# VerdiRT7_MainPCB.net
KiCad netlist of a schematic drawn in EAGLE
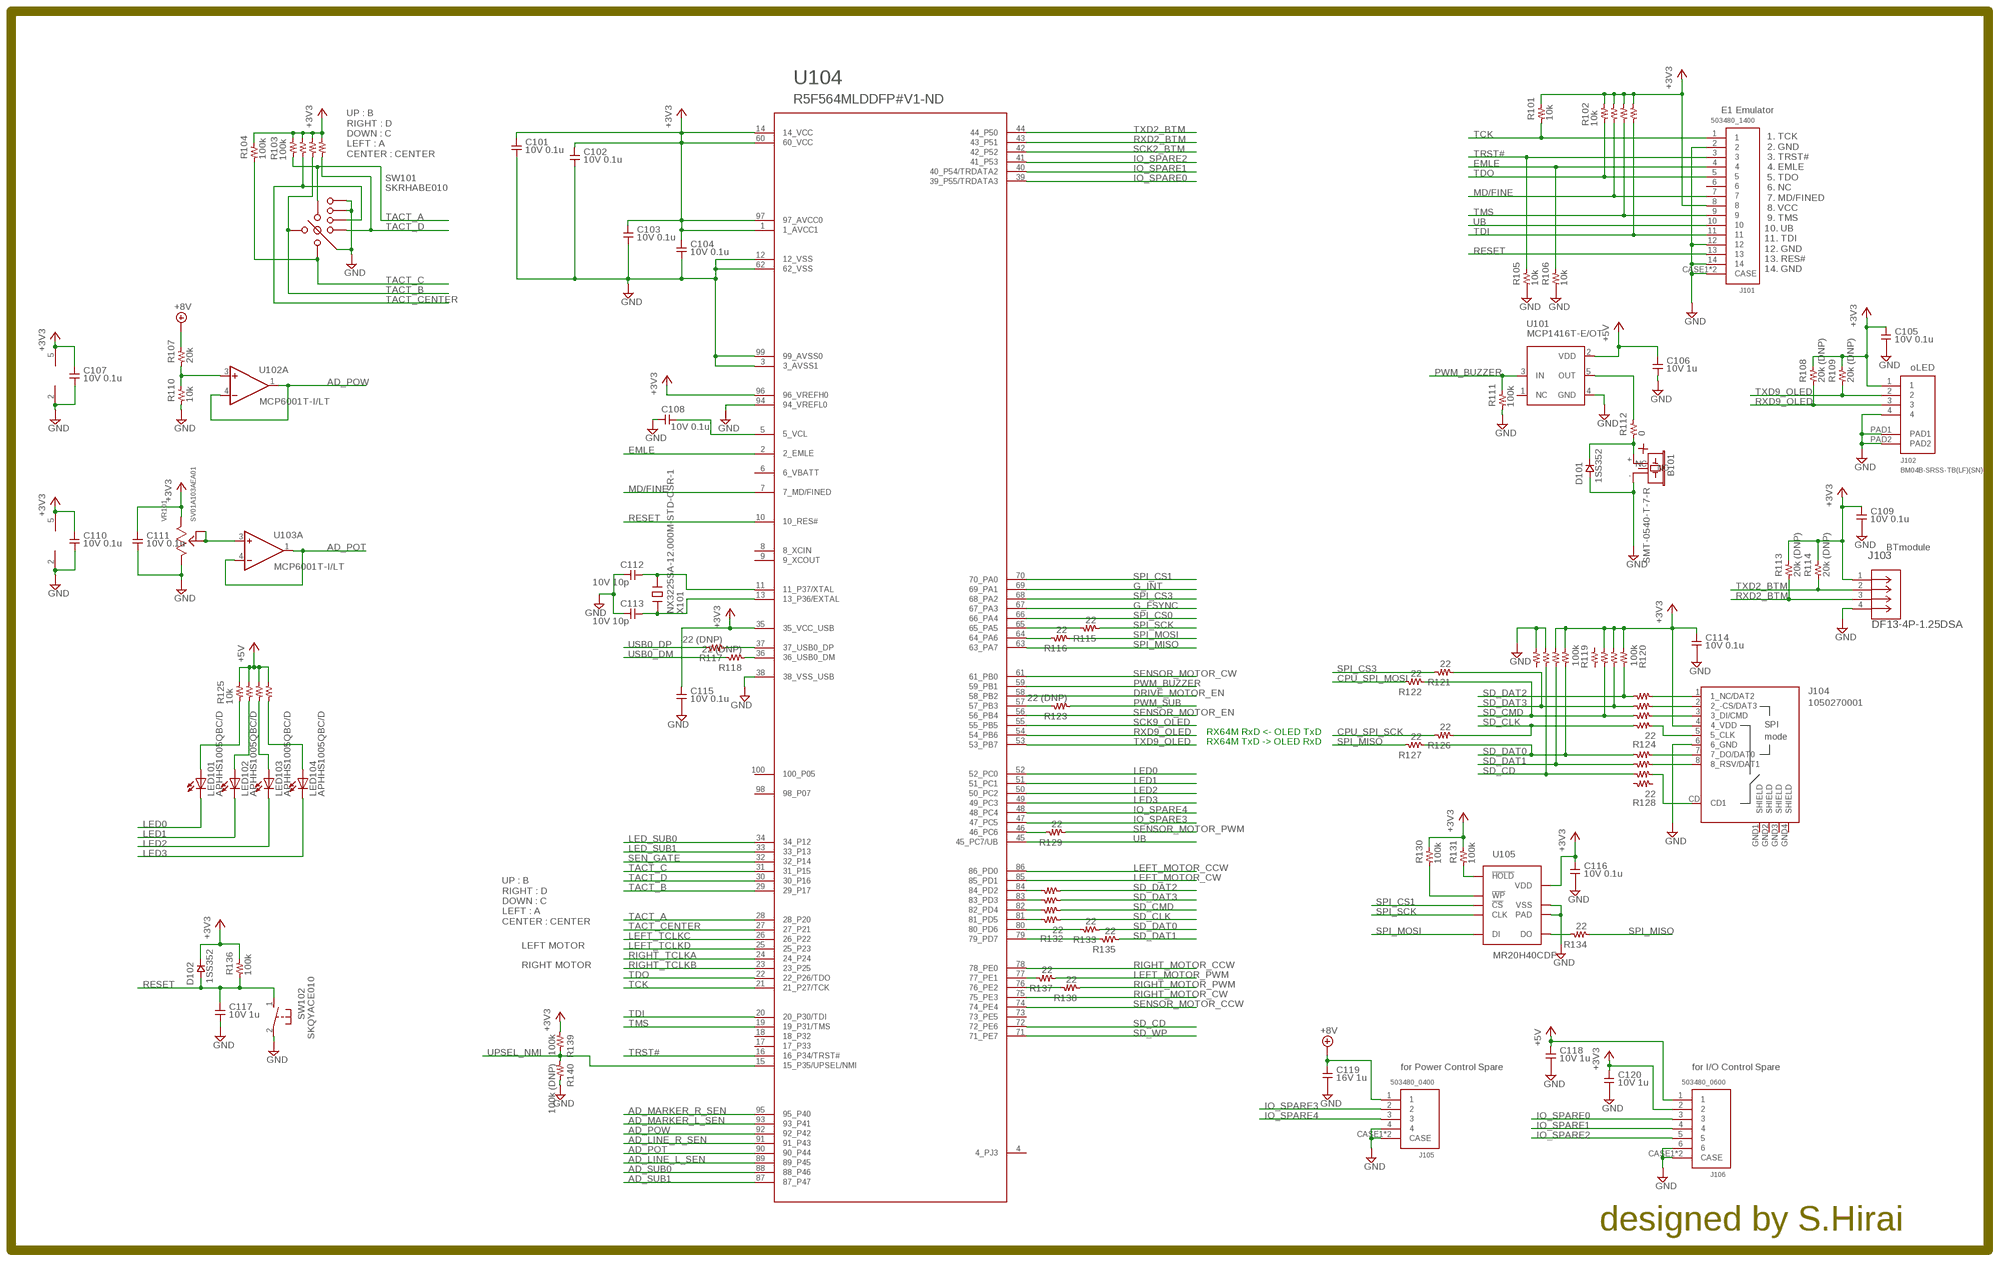
[diagram p0: schematic, sheet 1]
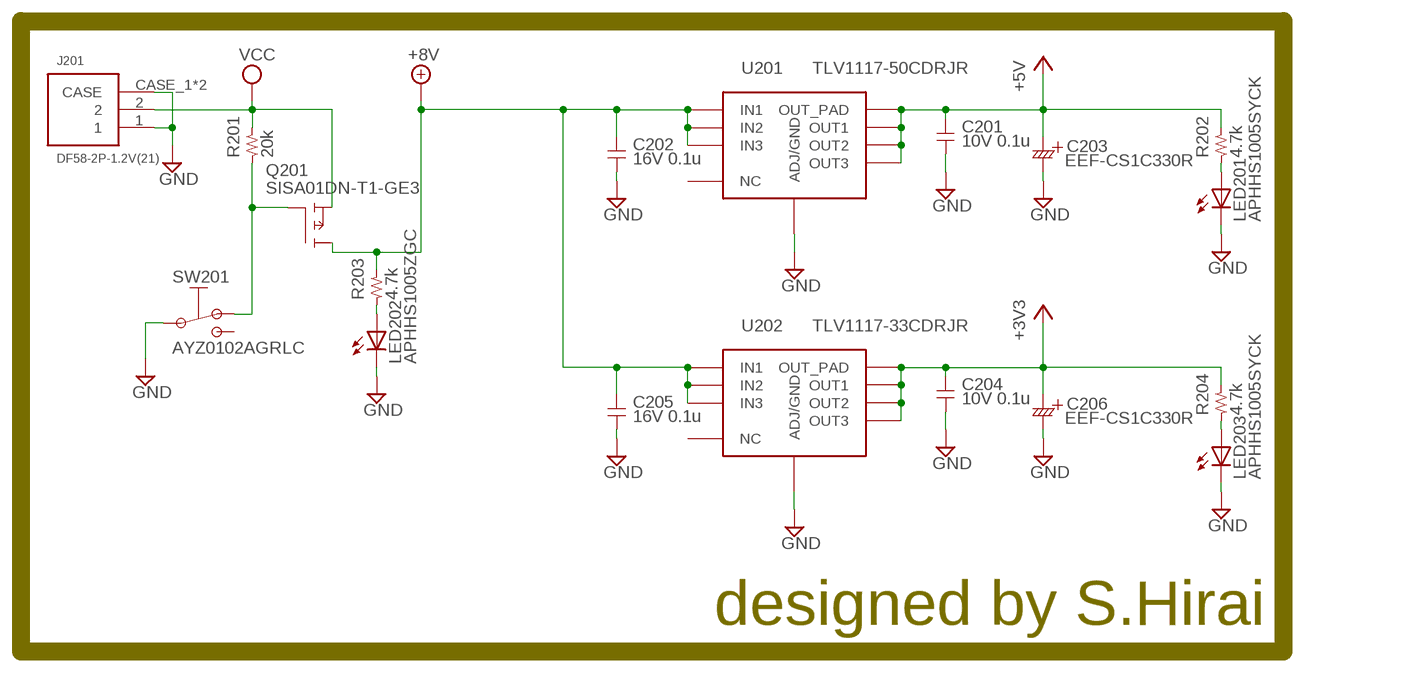
[diagram p1: schematic, sheet 2]
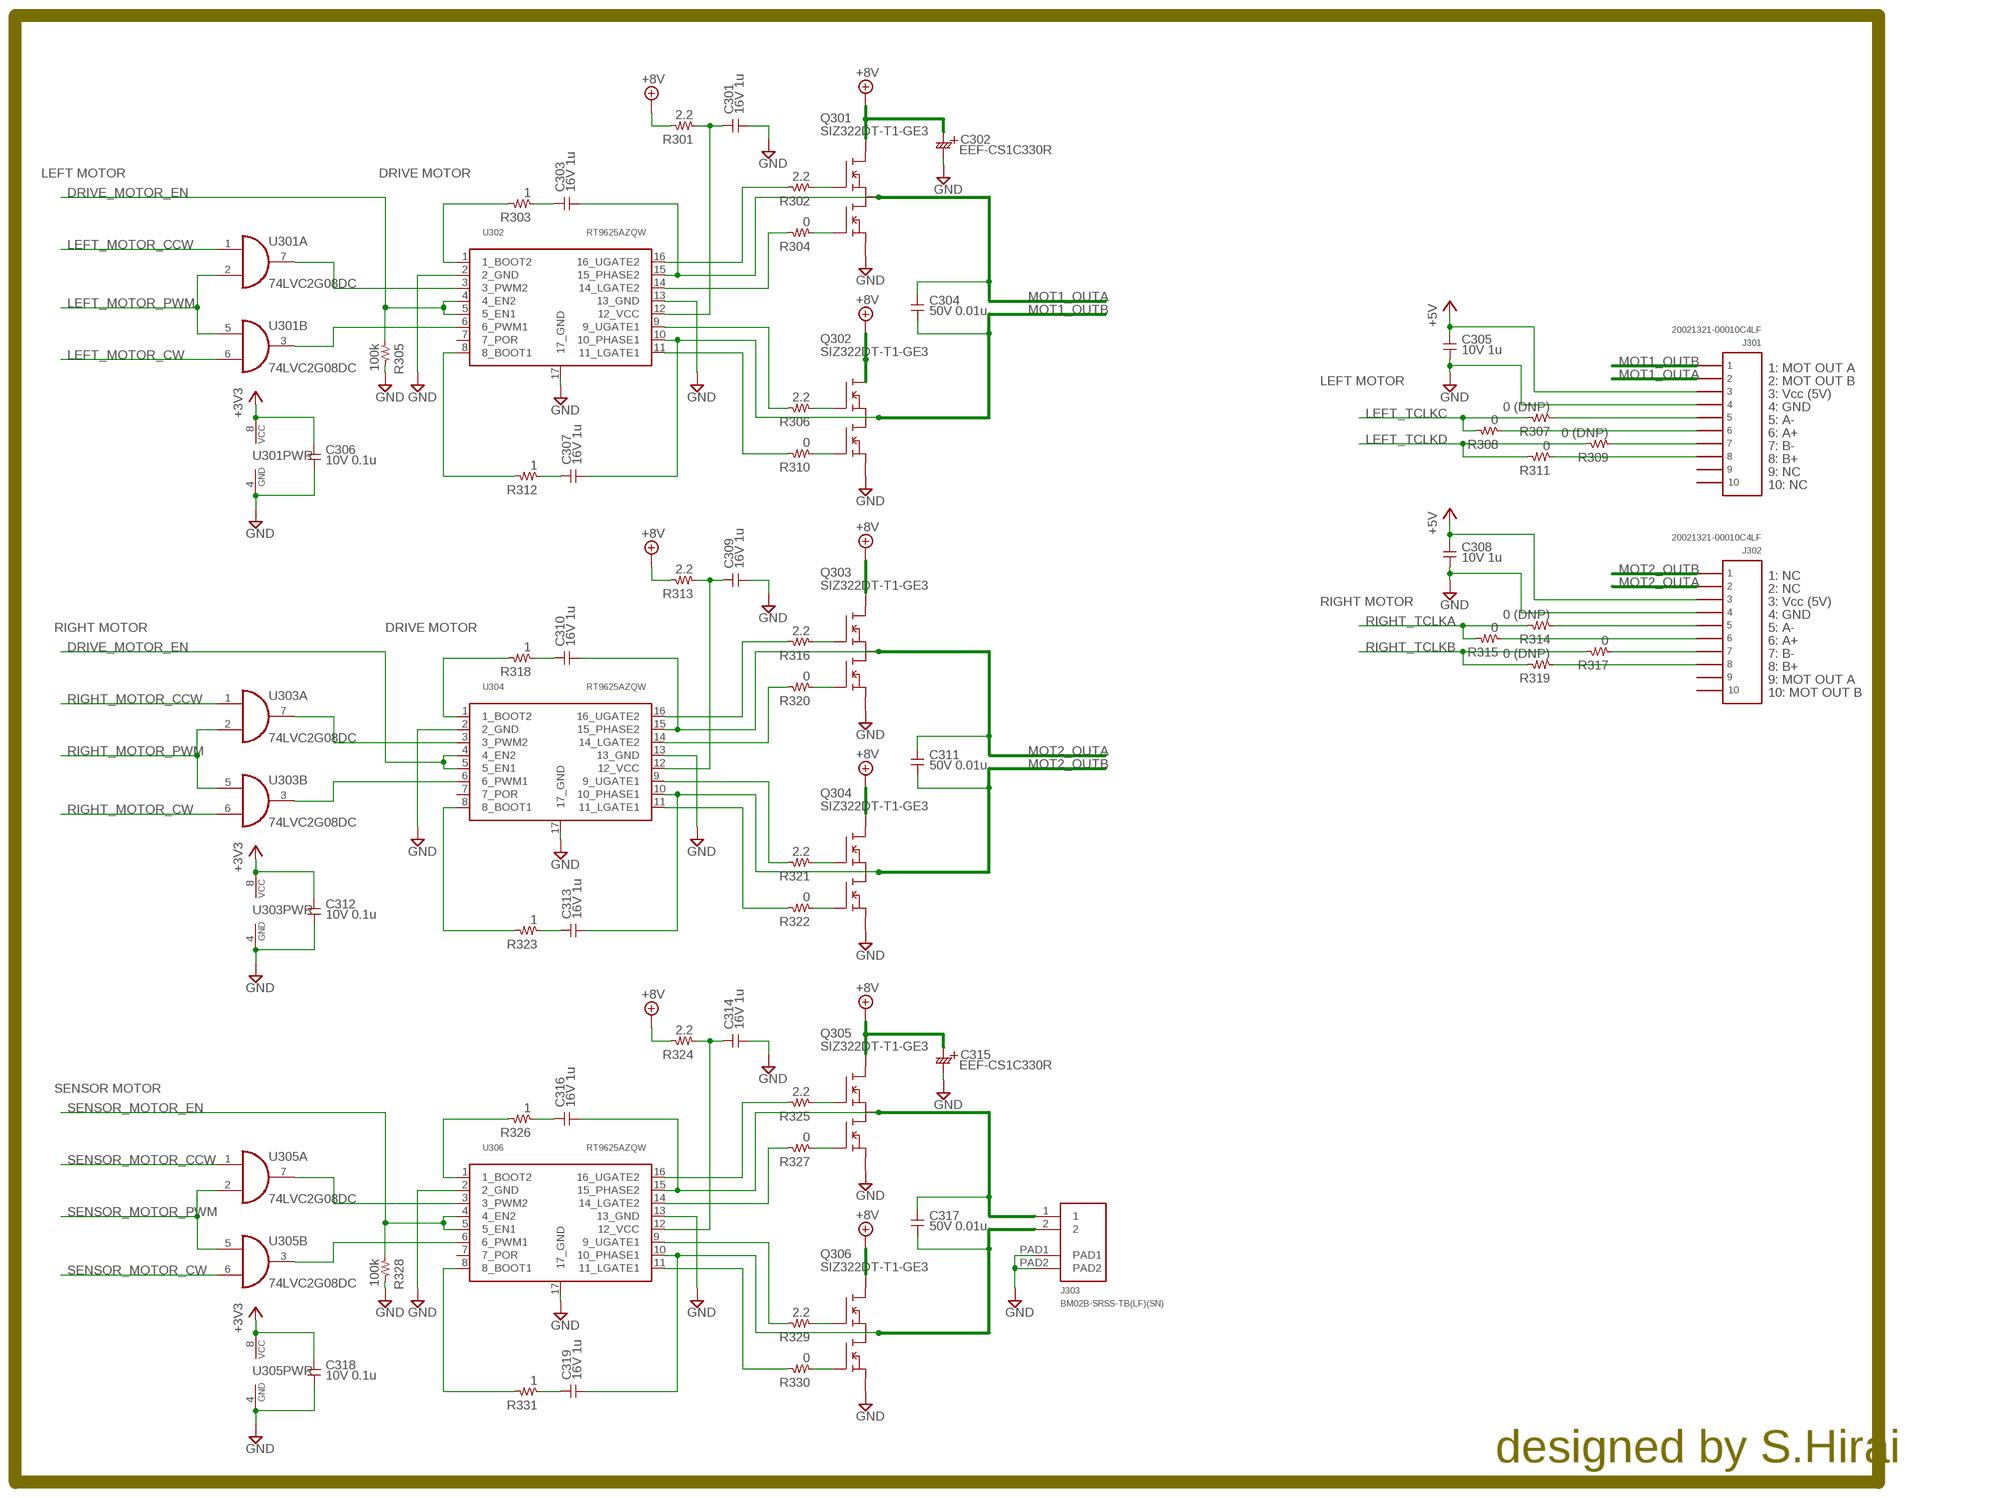
[diagram p2: schematic, sheet 3]
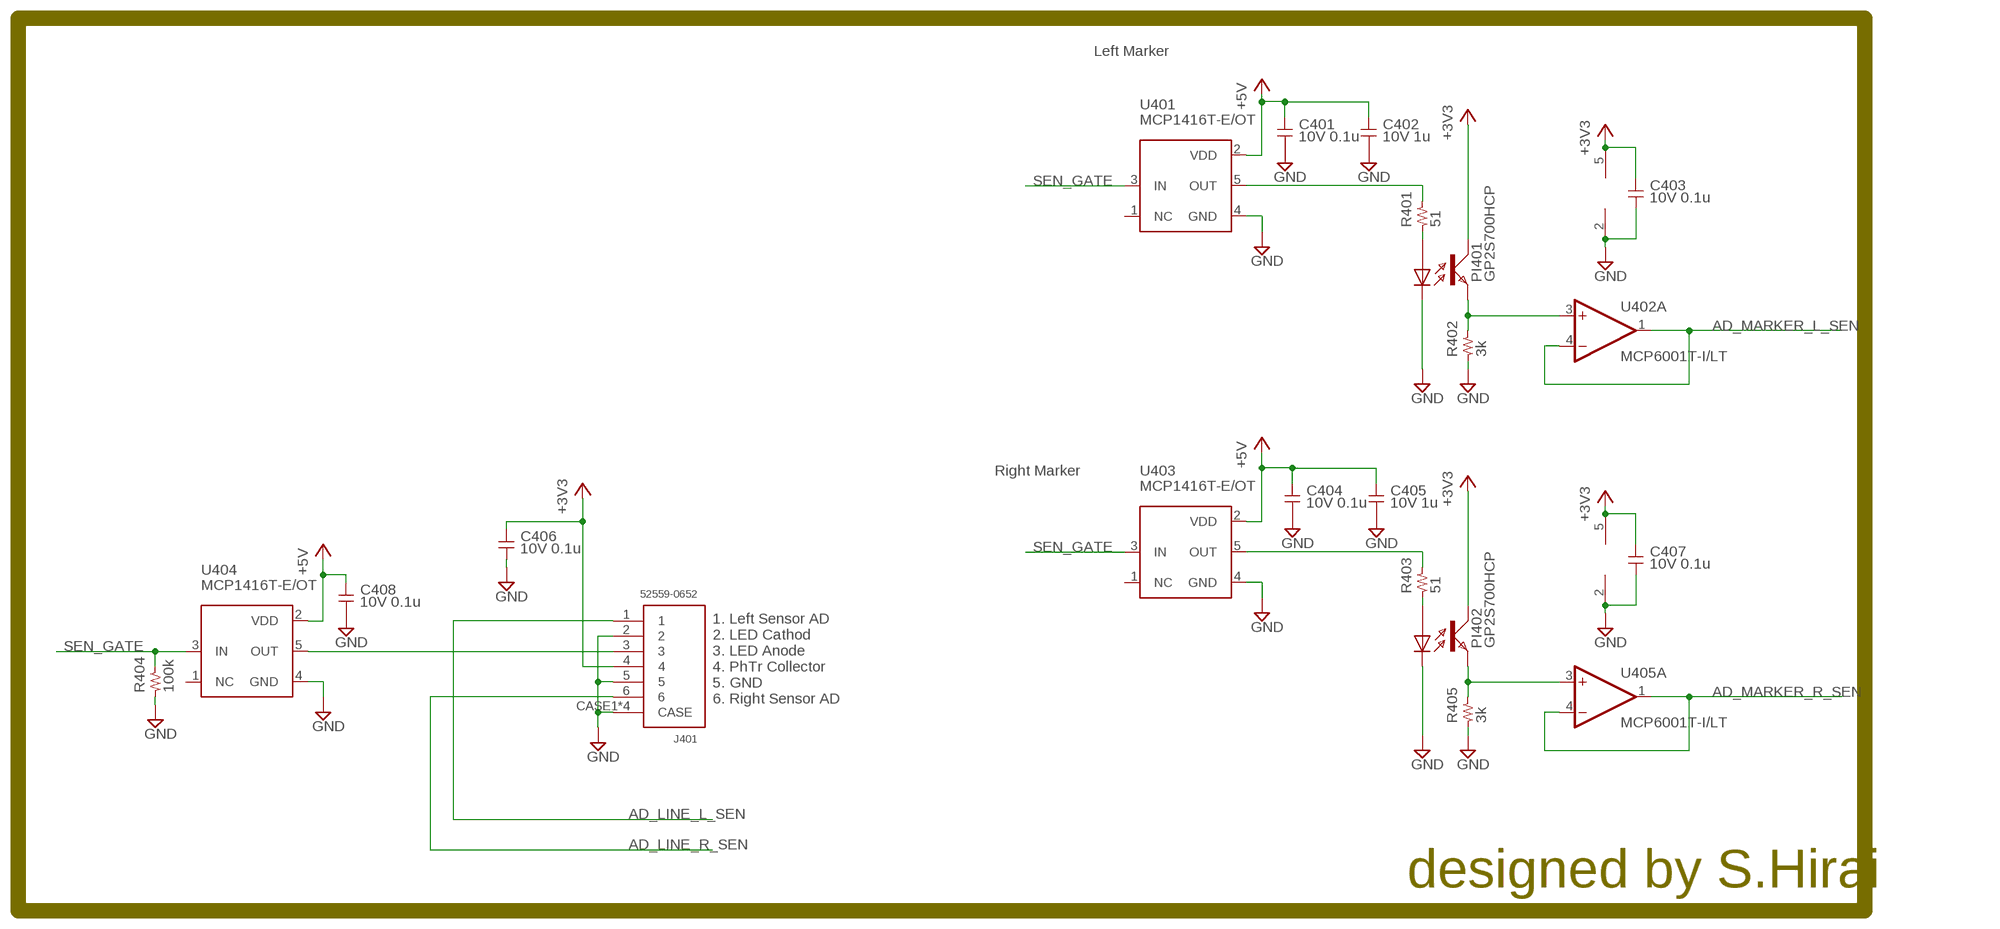
[diagram p3: schematic, sheet 4]
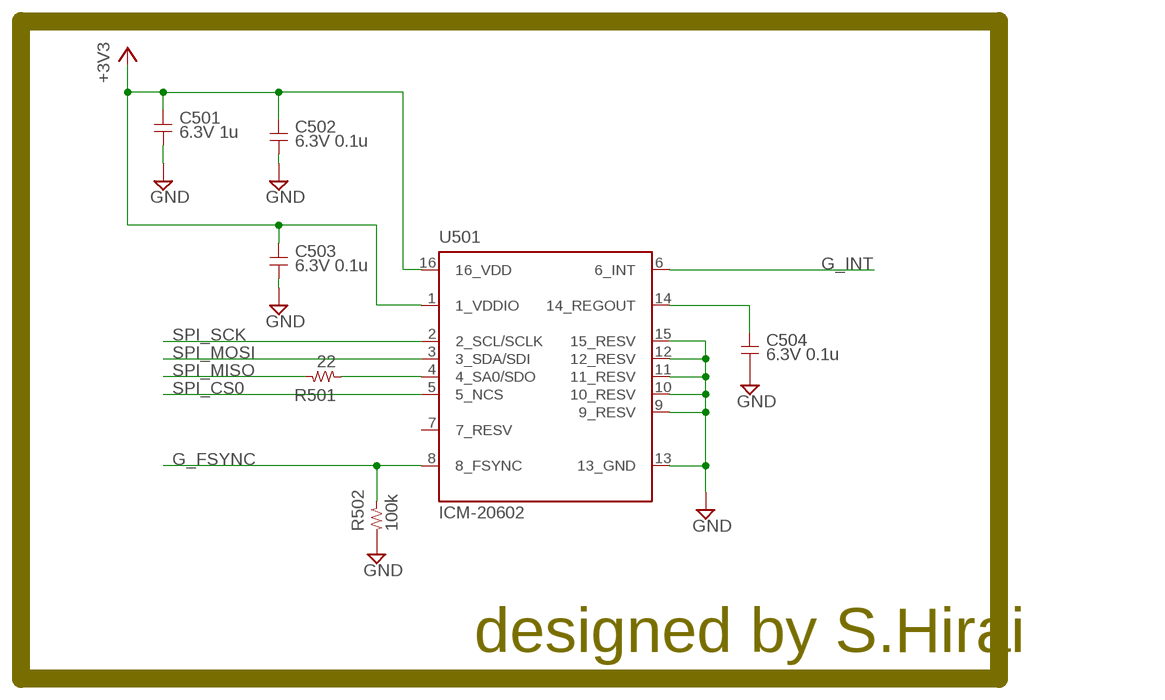
[diagram p4: schematic, sheet 5]
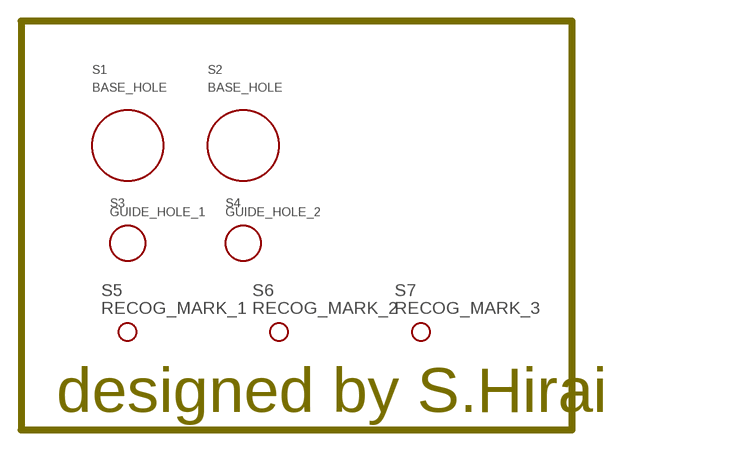
[diagram p5: schematic, sheet 6]

(export (version "E")
  (design (tool "Eeschema 10.0.6"))
  (components
    (comp (ref "C301")
      (value "16V 1u")
      (footprint "eagle-import:1005")
      (libsource (lib "eagle-import") (part "1005"))
    )
    (comp (ref "C302")
      (value "EEF-CS1C330R")
      (footprint "eagle-import:EEFC_7343")
      (fields (field (name "VOLTAGE") "16V"))
      (libsource (lib "eagle-import") (part "EEF-C?RS1C330"))
    )
    (comp (ref "C303")
      (value "16V 1u")
      (footprint "eagle-import:1005")
      (libsource (lib "eagle-import") (part "1005"))
    )
    (comp (ref "C304")
      (value "50V 0.01u")
      (footprint "eagle-import:1005")
      (libsource (lib "eagle-import") (part "1005"))
    )
    (comp (ref "C305")
      (value "10V 1u")
      (footprint "eagle-import:1005")
      (libsource (lib "eagle-import") (part "1005"))
    )
    (comp (ref "C306")
      (value "10V 0.1u")
      (footprint "eagle-import:1005")
      (libsource (lib "eagle-import") (part "1005"))
    )
    (comp (ref "C307")
      (value "16V 1u")
      (footprint "eagle-import:1005")
      (libsource (lib "eagle-import") (part "1005"))
    )
    (comp (ref "C308")
      (value "10V 1u")
      (footprint "eagle-import:1005")
      (libsource (lib "eagle-import") (part "1005"))
    )
    (comp (ref "C309")
      (value "16V 1u")
      (footprint "eagle-import:1005")
      (libsource (lib "eagle-import") (part "1005"))
    )
    (comp (ref "C310")
      (value "16V 1u")
      (footprint "eagle-import:1005")
      (libsource (lib "eagle-import") (part "1005"))
    )
    (comp (ref "C311")
      (value "50V 0.01u")
      (footprint "eagle-import:1005")
      (libsource (lib "eagle-import") (part "1005"))
    )
    (comp (ref "C312")
      (value "10V 0.1u")
      (footprint "eagle-import:1005")
      (libsource (lib "eagle-import") (part "1005"))
    )
    (comp (ref "C313")
      (value "16V 1u")
      (footprint "eagle-import:1005")
      (libsource (lib "eagle-import") (part "1005"))
    )
    (comp (ref "C314")
      (value "16V 1u")
      (footprint "eagle-import:1005")
      (libsource (lib "eagle-import") (part "1005"))
    )
    (comp (ref "C315")
      (value "EEF-CS1C330R")
      (footprint "eagle-import:EEFC_7343")
      (fields (field (name "VOLTAGE") "16V"))
      (libsource (lib "eagle-import") (part "EEF-C?RS1C330"))
    )
    (comp (ref "C316")
      (value "16V 1u")
      (footprint "eagle-import:1005")
      (libsource (lib "eagle-import") (part "1005"))
    )
    (comp (ref "C317")
      (value "50V 0.01u")
      (footprint "eagle-import:1005")
      (libsource (lib "eagle-import") (part "1005"))
    )
    (comp (ref "C318")
      (value "10V 0.1u")
      (footprint "eagle-import:1005")
      (libsource (lib "eagle-import") (part "1005"))
    )
    (comp (ref "C319")
      (value "16V 1u")
      (footprint "eagle-import:1005")
      (libsource (lib "eagle-import") (part "1005"))
    )
    (comp (ref "J301")
      (value "20021321-00010C4LF")
      (footprint "eagle-import:MA5-2_SMD_1.27MM_MIN")
      (libsource (lib "eagle-import") (part "20021321-00010C4LF"))
    )
    (comp (ref "J302")
      (value "20021321-00010C4LF")
      (footprint "eagle-import:MA5-2_SMD_1.27MM_MIN")
      (libsource (lib "eagle-import") (part "20021321-00010C4LF"))
    )
    (comp (ref "J303")
      (value "BM02B-SRSS-TB(LF)(SN)")
      (footprint "eagle-import:BM02B-SRSS-TB")
      (libsource (lib "eagle-import") (part "?M02B-SRSS-TB(LF)(SN)B"))
    )
    (comp (ref "Q301")
      (value "SIZ322DT-T1-GE3")
      (footprint "eagle-import:DFN3X3A")
      (libsource (lib "eagle-import") (part "SIZ322DT-T1-GE3"))
    )
    (comp (ref "Q302")
      (value "SIZ322DT-T1-GE3")
      (footprint "eagle-import:DFN3X3A")
      (libsource (lib "eagle-import") (part "SIZ322DT-T1-GE3"))
    )
    (comp (ref "Q303")
      (value "SIZ322DT-T1-GE3")
      (footprint "eagle-import:DFN3X3A")
      (libsource (lib "eagle-import") (part "SIZ322DT-T1-GE3"))
    )
    (comp (ref "Q304")
      (value "SIZ322DT-T1-GE3")
      (footprint "eagle-import:DFN3X3A")
      (libsource (lib "eagle-import") (part "SIZ322DT-T1-GE3"))
    )
    (comp (ref "Q305")
      (value "SIZ322DT-T1-GE3")
      (footprint "eagle-import:DFN3X3A")
      (libsource (lib "eagle-import") (part "SIZ322DT-T1-GE3"))
    )
    (comp (ref "Q306")
      (value "SIZ322DT-T1-GE3")
      (footprint "eagle-import:DFN3X3A")
      (libsource (lib "eagle-import") (part "SIZ322DT-T1-GE3"))
    )
    (comp (ref "R301")
      (value "2.2")
      (footprint "eagle-import:1005")
      (libsource (lib "eagle-import") (part "R1005"))
    )
    (comp (ref "R302")
      (value "2.2")
      (footprint "eagle-import:1005")
      (libsource (lib "eagle-import") (part "R1005"))
    )
    (comp (ref "R303")
      (value "1")
      (footprint "eagle-import:1005")
      (libsource (lib "eagle-import") (part "R1005"))
    )
    (comp (ref "R304")
      (value "0")
      (footprint "eagle-import:1005")
      (libsource (lib "eagle-import") (part "R1005"))
    )
    (comp (ref "R305")
      (value "100k")
      (footprint "eagle-import:1005")
      (libsource (lib "eagle-import") (part "R1005"))
    )
    (comp (ref "R306")
      (value "2.2")
      (footprint "eagle-import:1005")
      (libsource (lib "eagle-import") (part "R1005"))
    )
    (comp (ref "R307")
      (value "0 (DNP)")
      (footprint "eagle-import:1005")
      (libsource (lib "eagle-import") (part "R1005"))
    )
    (comp (ref "R308")
      (value "0")
      (footprint "eagle-import:1005")
      (libsource (lib "eagle-import") (part "R1005"))
    )
    (comp (ref "R309")
      (value "0 (DNP)")
      (footprint "eagle-import:1005")
      (libsource (lib "eagle-import") (part "R1005"))
    )
    (comp (ref "R310")
      (value "0")
      (footprint "eagle-import:1005")
      (libsource (lib "eagle-import") (part "R1005"))
    )
    (comp (ref "R311")
      (value "0")
      (footprint "eagle-import:1005")
      (libsource (lib "eagle-import") (part "R1005"))
    )
    (comp (ref "R312")
      (value "1")
      (footprint "eagle-import:1005")
      (libsource (lib "eagle-import") (part "R1005"))
    )
    (comp (ref "R313")
      (value "2.2")
      (footprint "eagle-import:1005")
      (libsource (lib "eagle-import") (part "R1005"))
    )
    (comp (ref "R314")
      (value "0 (DNP)")
      (footprint "eagle-import:1005")
      (libsource (lib "eagle-import") (part "R1005"))
    )
    (comp (ref "R315")
      (value "0")
      (footprint "eagle-import:1005")
      (libsource (lib "eagle-import") (part "R1005"))
    )
    (comp (ref "R316")
      (value "2.2")
      (footprint "eagle-import:1005")
      (libsource (lib "eagle-import") (part "R1005"))
    )
    (comp (ref "R317")
      (value "0")
      (footprint "eagle-import:1005")
      (libsource (lib "eagle-import") (part "R1005"))
    )
    (comp (ref "R318")
      (value "1")
      (footprint "eagle-import:1005")
      (libsource (lib "eagle-import") (part "R1005"))
    )
    (comp (ref "R319")
      (value "0 (DNP)")
      (footprint "eagle-import:1005")
      (libsource (lib "eagle-import") (part "R1005"))
    )
    (comp (ref "R320")
      (value "0")
      (footprint "eagle-import:1005")
      (libsource (lib "eagle-import") (part "R1005"))
    )
    (comp (ref "R321")
      (value "2.2")
      (footprint "eagle-import:1005")
      (libsource (lib "eagle-import") (part "R1005"))
    )
    (comp (ref "R322")
      (value "0")
      (footprint "eagle-import:1005")
      (libsource (lib "eagle-import") (part "R1005"))
    )
    (comp (ref "R323")
      (value "1")
      (footprint "eagle-import:1005")
      (libsource (lib "eagle-import") (part "R1005"))
    )
    (comp (ref "R324")
      (value "2.2")
      (footprint "eagle-import:1005")
      (libsource (lib "eagle-import") (part "R1005"))
    )
    (comp (ref "R325")
      (value "2.2")
      (footprint "eagle-import:1005")
      (libsource (lib "eagle-import") (part "R1005"))
    )
    (comp (ref "R326")
      (value "1")
      (footprint "eagle-import:1005")
      (libsource (lib "eagle-import") (part "R1005"))
    )
    (comp (ref "R327")
      (value "0")
      (footprint "eagle-import:1005")
      (libsource (lib "eagle-import") (part "R1005"))
    )
    (comp (ref "R328")
      (value "100k")
      (footprint "eagle-import:1005")
      (libsource (lib "eagle-import") (part "R1005"))
    )
    (comp (ref "R329")
      (value "2.2")
      (footprint "eagle-import:1005")
      (libsource (lib "eagle-import") (part "R1005"))
    )
    (comp (ref "R330")
      (value "0")
      (footprint "eagle-import:1005")
      (libsource (lib "eagle-import") (part "R1005"))
    )
    (comp (ref "R331")
      (value "1")
      (footprint "eagle-import:1005")
      (libsource (lib "eagle-import") (part "R1005"))
    )
    (comp (ref "U301")
      (value "74LVC2G08DC")
      (footprint "eagle-import:VSSOP8")
      (libsource (lib "eagle-import") (part "74LVC2G08DC"))
    )
    (comp (ref "U302")
      (value "RT9625AZQW")
      (footprint "eagle-import:WQFN16")
      (libsource (lib "eagle-import") (part "RT9625AZQW"))
    )
    (comp (ref "U303")
      (value "74LVC2G08DC")
      (footprint "eagle-import:VSSOP8")
      (libsource (lib "eagle-import") (part "74LVC2G08DC"))
    )
    (comp (ref "U304")
      (value "RT9625AZQW")
      (footprint "eagle-import:WQFN16")
      (libsource (lib "eagle-import") (part "RT9625AZQW"))
    )
    (comp (ref "U305")
      (value "74LVC2G08DC")
      (footprint "eagle-import:VSSOP8")
      (libsource (lib "eagle-import") (part "74LVC2G08DC"))
    )
    (comp (ref "U306")
      (value "RT9625AZQW")
      (footprint "eagle-import:WQFN16")
      (libsource (lib "eagle-import") (part "RT9625AZQW"))
    )
    (comp (ref "C501")
      (value "6.3V 1u")
      (footprint "eagle-import:1005")
      (libsource (lib "eagle-import") (part "1005"))
    )
    (comp (ref "C502")
      (value "6.3V 0.1u")
      (footprint "eagle-import:1005")
      (libsource (lib "eagle-import") (part "1005"))
    )
    (comp (ref "C503")
      (value "6.3V 0.1u")
      (footprint "eagle-import:1005")
      (libsource (lib "eagle-import") (part "1005"))
    )
    (comp (ref "C504")
      (value "6.3V 0.1u")
      (footprint "eagle-import:1005")
      (libsource (lib "eagle-import") (part "1005"))
    )
    (comp (ref "R501")
      (value "22")
      (footprint "eagle-import:1005")
      (libsource (lib "eagle-import") (part "R1005"))
    )
    (comp (ref "R502")
      (value "100k")
      (footprint "eagle-import:1005")
      (libsource (lib "eagle-import") (part "R1005"))
    )
    (comp (ref "U501")
      (value "ICM-20602")
      (footprint "eagle-import:LGA16_3X3MM")
      (libsource (lib "eagle-import") (part "ICM-20602"))
    )
    (comp (ref "C401")
      (value "10V 0.1u")
      (footprint "eagle-import:1005")
      (libsource (lib "eagle-import") (part "1005"))
    )
    (comp (ref "C402")
      (value "10V 1u")
      (footprint "eagle-import:1005")
      (libsource (lib "eagle-import") (part "1005"))
    )
    (comp (ref "C403")
      (value "10V 0.1u")
      (footprint "eagle-import:1005")
      (libsource (lib "eagle-import") (part "1005"))
    )
    (comp (ref "C404")
      (value "10V 0.1u")
      (footprint "eagle-import:1005")
      (libsource (lib "eagle-import") (part "1005"))
    )
    (comp (ref "C405")
      (value "10V 1u")
      (footprint "eagle-import:1005")
      (libsource (lib "eagle-import") (part "1005"))
    )
    (comp (ref "C406")
      (value "10V 0.1u")
      (footprint "eagle-import:1005")
      (libsource (lib "eagle-import") (part "1005"))
    )
    (comp (ref "C407")
      (value "10V 0.1u")
      (footprint "eagle-import:1005")
      (libsource (lib "eagle-import") (part "1005"))
    )
    (comp (ref "C408")
      (value "10V 0.1u")
      (footprint "eagle-import:1005")
      (libsource (lib "eagle-import") (part "1005"))
    )
    (comp (ref "J401")
      (value "52559-0652")
      (footprint "eagle-import:0652")
      (libsource (lib "eagle-import") (part "52559-0652"))
    )
    (comp (ref "PI401")
      (value "GP2S700HCP")
      (footprint "eagle-import:GP2S700")
      (libsource (lib "eagle-import") (part "GP2S700HCP"))
    )
    (comp (ref "PI402")
      (value "GP2S700HCP")
      (footprint "eagle-import:GP2S700")
      (libsource (lib "eagle-import") (part "GP2S700HCP"))
    )
    (comp (ref "R401")
      (value "51")
      (footprint "eagle-import:1608")
      (libsource (lib "eagle-import") (part "R1608"))
    )
    (comp (ref "R402")
      (value "3k")
      (footprint "eagle-import:1005")
      (libsource (lib "eagle-import") (part "R1005"))
    )
    (comp (ref "R403")
      (value "51")
      (footprint "eagle-import:1608")
      (libsource (lib "eagle-import") (part "R1608"))
    )
    (comp (ref "R404")
      (value "100k")
      (footprint "eagle-import:1005")
      (libsource (lib "eagle-import") (part "R1005"))
    )
    (comp (ref "R405")
      (value "3k")
      (footprint "eagle-import:1005")
      (libsource (lib "eagle-import") (part "R1005"))
    )
    (comp (ref "U401")
      (value "MCP1416T-E/OT")
      (footprint "eagle-import:SOT23-5")
      (libsource (lib "eagle-import") (part "MCP1416?T-E/OT"))
    )
    (comp (ref "U402")
      (value "MCP6001T-I/LT")
      (footprint "eagle-import:SOT-70-5")
      (libsource (lib "eagle-import") (part "MCP6001?-TI/LT"))
    )
    (comp (ref "U403")
      (value "MCP1416T-E/OT")
      (footprint "eagle-import:SOT23-5")
      (libsource (lib "eagle-import") (part "MCP1416?T-E/OT"))
    )
    (comp (ref "U404")
      (value "MCP1416T-E/OT")
      (footprint "eagle-import:SOT23-5")
      (libsource (lib "eagle-import") (part "MCP1416?T-E/OT"))
    )
    (comp (ref "U405")
      (value "MCP6001T-I/LT")
      (footprint "eagle-import:SOT-70-5")
      (libsource (lib "eagle-import") (part "MCP6001?-TI/LT"))
    )
    (comp (ref "C201")
      (value "10V 0.1u")
      (footprint "eagle-import:1005")
      (libsource (lib "eagle-import") (part "1005"))
    )
    (comp (ref "C202")
      (value "16V 0.1u")
      (footprint "eagle-import:1005")
      (libsource (lib "eagle-import") (part "1005"))
    )
    (comp (ref "C203")
      (value "EEF-CS1C330R")
      (footprint "eagle-import:EEFC_7343")
      (fields (field (name "VOLTAGE") "16V"))
      (libsource (lib "eagle-import") (part "EEF-C?RS1C330"))
    )
    (comp (ref "C204")
      (value "10V 0.1u")
      (footprint "eagle-import:1005")
      (libsource (lib "eagle-import") (part "1005"))
    )
    (comp (ref "C205")
      (value "16V 0.1u")
      (footprint "eagle-import:1005")
      (libsource (lib "eagle-import") (part "1005"))
    )
    (comp (ref "C206")
      (value "EEF-CS1C330R")
      (footprint "eagle-import:EEFC_7343")
      (fields (field (name "VOLTAGE") "16V"))
      (libsource (lib "eagle-import") (part "EEF-C?RS1C330"))
    )
    (comp (ref "J201")
      (value "DF58-2P-1.2V(21)")
      (footprint "eagle-import:DF58_2P")
      (libsource (lib "eagle-import") (part "DF58-2P-1.2V(21)"))
    )
    (comp (ref "LED201")
      (value "APHHS1005SYCK")
      (footprint "eagle-import:1005")
      (libsource (lib "eagle-import") (part "LED1005"))
    )
    (comp (ref "LED202")
      (value "APHHS1005ZGC")
      (footprint "eagle-import:1005")
      (libsource (lib "eagle-import") (part "LED1005"))
    )
    (comp (ref "LED203")
      (value "APHHS1005SYCK")
      (footprint "eagle-import:1005")
      (libsource (lib "eagle-import") (part "LED1005"))
    )
    (comp (ref "Q201")
      (value "SISA01DN-T1-GE3")
      (footprint "eagle-import:POWERPAK1212-8")
      (libsource (lib "eagle-import") (part "SISA01DN-T1-GE3"))
    )
    (comp (ref "R201")
      (value "20k")
      (footprint "eagle-import:1005")
      (libsource (lib "eagle-import") (part "R1005"))
    )
    (comp (ref "R202")
      (value "4.7k")
      (footprint "eagle-import:1005")
      (libsource (lib "eagle-import") (part "R1005"))
    )
    (comp (ref "R203")
      (value "4.7k")
      (footprint "eagle-import:1005")
      (libsource (lib "eagle-import") (part "R1005"))
    )
    (comp (ref "R204")
      (value "4.7k")
      (footprint "eagle-import:1005")
      (libsource (lib "eagle-import") (part "R1005"))
    )
    (comp (ref "SW201")
      (value "AYZ0102AGRLC")
      (footprint "eagle-import:AYZ0102AGRLC")
      (libsource (lib "eagle-import") (part "AYZ0102AGRLC"))
    )
    (comp (ref "U201")
      (value "TLV1117-50CDRJR")
      (footprint "eagle-import:WFDFN8")
      (libsource (lib "eagle-import") (part "TLV1117-DRJR50C"))
    )
    (comp (ref "U202")
      (value "TLV1117-33CDRJR")
      (footprint "eagle-import:WFDFN8")
      (libsource (lib "eagle-import") (part "TLV1117-DRJR33C"))
    )
    (comp (ref "S1")
      (value "BASE_HOLE")
      (footprint "eagle-import:BASE_HOLE")
      (libsource (lib "eagle-import") (part "BASE_HOLE"))
    )
    (comp (ref "S2")
      (value "BASE_HOLE")
      (footprint "eagle-import:BASE_HOLE")
      (libsource (lib "eagle-import") (part "BASE_HOLE"))
    )
    (comp (ref "S3")
      (value "GUIDE_HOLE_1")
      (footprint "eagle-import:GUIDE_HOLE")
      (libsource (lib "eagle-import") (part "GUIDE_HOLE_1"))
    )
    (comp (ref "S4")
      (value "GUIDE_HOLE_2")
      (footprint "eagle-import:GUIDE_HOLE")
      (libsource (lib "eagle-import") (part "GUIDE_HOLE_2"))
    )
    (comp (ref "S5")
      (value "RECOG_MARK_1")
      (footprint "eagle-import:RECOG_MARK")
      (libsource (lib "eagle-import") (part "RECOG_MARK_1"))
    )
    (comp (ref "S6")
      (value "RECOG_MARK_2")
      (footprint "eagle-import:RECOG_MARK")
      (libsource (lib "eagle-import") (part "RECOG_MARK_2"))
    )
    (comp (ref "S7")
      (value "RECOG_MARK_3")
      (footprint "eagle-import:RECOG_MARK")
      (libsource (lib "eagle-import") (part "RECOG_MARK_3"))
    )
    (comp (ref "B101")
      (value "SMT-0540-T-7-R")
      (footprint "eagle-import:SMT-0540-S-R")
      (libsource (lib "eagle-import") (part "SMT-0540-T-7-R"))
    )
    (comp (ref "C101")
      (value "10V 0.1u")
      (footprint "eagle-import:1005")
      (libsource (lib "eagle-import") (part "1005"))
    )
    (comp (ref "C102")
      (value "10V 0.1u")
      (footprint "eagle-import:1005")
      (libsource (lib "eagle-import") (part "1005"))
    )
    (comp (ref "C103")
      (value "10V 0.1u")
      (footprint "eagle-import:1005")
      (libsource (lib "eagle-import") (part "1005"))
    )
    (comp (ref "C104")
      (value "10V 0.1u")
      (footprint "eagle-import:1005")
      (libsource (lib "eagle-import") (part "1005"))
    )
    (comp (ref "C105")
      (value "10V 0.1u")
      (footprint "eagle-import:1005")
      (libsource (lib "eagle-import") (part "1005"))
    )
    (comp (ref "C106")
      (value "10V 1u")
      (footprint "eagle-import:1005")
      (libsource (lib "eagle-import") (part "1005"))
    )
    (comp (ref "C107")
      (value "10V 0.1u")
      (footprint "eagle-import:1005")
      (libsource (lib "eagle-import") (part "1005"))
    )
    (comp (ref "C108")
      (value "10V 0.1u")
      (footprint "eagle-import:1005")
      (libsource (lib "eagle-import") (part "1005"))
    )
    (comp (ref "C109")
      (value "10V 0.1u")
      (footprint "eagle-import:1005")
      (libsource (lib "eagle-import") (part "1005"))
    )
    (comp (ref "C110")
      (value "10V 0.1u")
      (footprint "eagle-import:1005")
      (libsource (lib "eagle-import") (part "1005"))
    )
    (comp (ref "C111")
      (value "10V 0.1u")
      (footprint "eagle-import:1005")
      (libsource (lib "eagle-import") (part "1005"))
    )
    (comp (ref "C112")
      (value "10V 10p")
      (footprint "eagle-import:1005")
      (libsource (lib "eagle-import") (part "1005"))
    )
    (comp (ref "C113")
      (value "10V 10p")
      (footprint "eagle-import:1005")
      (libsource (lib "eagle-import") (part "1005"))
    )
    (comp (ref "C114")
      (value "10V 0.1u")
      (footprint "eagle-import:1005")
      (libsource (lib "eagle-import") (part "1005"))
    )
    (comp (ref "C115")
      (value "10V 0.1u")
      (footprint "eagle-import:1005")
      (libsource (lib "eagle-import") (part "1005"))
    )
    (comp (ref "C116")
      (value "10V 0.1u")
      (footprint "eagle-import:1005")
      (libsource (lib "eagle-import") (part "1005"))
    )
    (comp (ref "C117")
      (value "10V 1u")
      (footprint "eagle-import:1005")
      (libsource (lib "eagle-import") (part "1005"))
    )
    (comp (ref "C118")
      (value "10V 1u")
      (footprint "eagle-import:1005")
      (libsource (lib "eagle-import") (part "1005"))
    )
    (comp (ref "C119")
      (value "16V 1u")
      (footprint "eagle-import:1005")
      (libsource (lib "eagle-import") (part "1005"))
    )
    (comp (ref "C120")
      (value "10V 1u")
      (footprint "eagle-import:1005")
      (libsource (lib "eagle-import") (part "1005"))
    )
    (comp (ref "D101")
      (value "1SS352")
      (footprint "eagle-import:2012")
      (libsource (lib "eagle-import") (part "1SS352"))
    )
    (comp (ref "D102")
      (value "1SS352")
      (footprint "eagle-import:2012")
      (libsource (lib "eagle-import") (part "1SS352"))
    )
    (comp (ref "J101")
      (value "503480_1400")
      (footprint "eagle-import:1400")
      (libsource (lib "eagle-import") (part "503480_1400"))
    )
    (comp (ref "J102")
      (value "BM04B-SRSS-TB(LF)(SN)")
      (footprint "eagle-import:BM04B-SRSS-TB")
      (libsource (lib "eagle-import") (part "?M04B-SRSS-TB(LF)(SN)B"))
    )
    (comp (ref "J103")
      (value "DF13-4P-1.25DSA")
      (footprint "eagle-import:DF13_4P_TH")
      (libsource (lib "eagle-import") (part "DF13-4P-1.25DSA"))
    )
    (comp (ref "J104")
      (value "1050270001")
      (footprint "eagle-import:MOLEX_105027")
      (libsource (lib "eagle-import") (part "1050270001"))
    )
    (comp (ref "J105")
      (value "503480_0400")
      (footprint "eagle-import:0400")
      (libsource (lib "eagle-import") (part "503480_0400"))
    )
    (comp (ref "J106")
      (value "503480_0600")
      (footprint "eagle-import:0600")
      (libsource (lib "eagle-import") (part "503480_0600"))
    )
    (comp (ref "LED101")
      (value "APHHS1005QBC/D")
      (footprint "eagle-import:1005")
      (libsource (lib "eagle-import") (part "LED1005"))
    )
    (comp (ref "LED102")
      (value "APHHS1005QBC/D")
      (footprint "eagle-import:1005")
      (libsource (lib "eagle-import") (part "LED1005"))
    )
    (comp (ref "LED103")
      (value "APHHS1005QBC/D")
      (footprint "eagle-import:1005")
      (libsource (lib "eagle-import") (part "LED1005"))
    )
    (comp (ref "LED104")
      (value "APHHS1005QBC/D")
      (footprint "eagle-import:1005")
      (libsource (lib "eagle-import") (part "LED1005"))
    )
    (comp (ref "R101")
      (value "10k")
      (footprint "eagle-import:1005")
      (libsource (lib "eagle-import") (part "R1005"))
    )
    (comp (ref "R102")
      (value "10k")
      (footprint "eagle-import:3216_ARRAY")
      (libsource (lib "eagle-import") (part "3216_ARRAY"))
    )
    (comp (ref "R103")
      (value "100k")
      (footprint "eagle-import:3216_ARRAY")
      (libsource (lib "eagle-import") (part "3216_ARRAY"))
    )
    (comp (ref "R104")
      (value "100k")
      (footprint "eagle-import:1005")
      (libsource (lib "eagle-import") (part "R1005"))
    )
    (comp (ref "R105")
      (value "10k")
      (footprint "eagle-import:1005")
      (libsource (lib "eagle-import") (part "R1005"))
    )
    (comp (ref "R106")
      (value "10k")
      (footprint "eagle-import:1005")
      (libsource (lib "eagle-import") (part "R1005"))
    )
    (comp (ref "R107")
      (value "20k")
      (footprint "eagle-import:1005")
      (libsource (lib "eagle-import") (part "R1005"))
    )
    (comp (ref "R108")
      (value "20k (DNP)")
      (footprint "eagle-import:1005")
      (libsource (lib "eagle-import") (part "R1005"))
    )
    (comp (ref "R109")
      (value "20k (DNP)")
      (footprint "eagle-import:1005")
      (libsource (lib "eagle-import") (part "R1005"))
    )
    (comp (ref "R110")
      (value "10k")
      (footprint "eagle-import:1005")
      (libsource (lib "eagle-import") (part "R1005"))
    )
    (comp (ref "R111")
      (value "100k")
      (footprint "eagle-import:1005")
      (libsource (lib "eagle-import") (part "R1005"))
    )
    (comp (ref "R112")
      (value "0")
      (footprint "eagle-import:1005")
      (libsource (lib "eagle-import") (part "R1005"))
    )
    (comp (ref "R113")
      (value "20k (DNP)")
      (footprint "eagle-import:1005")
      (libsource (lib "eagle-import") (part "R1005"))
    )
    (comp (ref "R114")
      (value "20k (DNP)")
      (footprint "eagle-import:1005")
      (libsource (lib "eagle-import") (part "R1005"))
    )
    (comp (ref "R115")
      (value "22")
      (footprint "eagle-import:1005")
      (libsource (lib "eagle-import") (part "R1005"))
    )
    (comp (ref "R116")
      (value "22")
      (footprint "eagle-import:1005")
      (libsource (lib "eagle-import") (part "R1005"))
    )
    (comp (ref "R117")
      (value "22 (DNP)")
      (footprint "eagle-import:1005")
      (libsource (lib "eagle-import") (part "R1005"))
    )
    (comp (ref "R118")
      (value "22 (DNP)")
      (footprint "eagle-import:1005")
      (libsource (lib "eagle-import") (part "R1005"))
    )
    (comp (ref "R119")
      (value "100k")
      (footprint "eagle-import:3216_ARRAY")
      (libsource (lib "eagle-import") (part "3216_ARRAY"))
    )
    (comp (ref "R120")
      (value "100k")
      (footprint "eagle-import:3216_ARRAY")
      (libsource (lib "eagle-import") (part "3216_ARRAY"))
    )
    (comp (ref "R121")
      (value "22")
      (footprint "eagle-import:1005")
      (libsource (lib "eagle-import") (part "R1005"))
    )
    (comp (ref "R122")
      (value "22")
      (footprint "eagle-import:1005")
      (libsource (lib "eagle-import") (part "R1005"))
    )
    (comp (ref "R123")
      (value "22 (DNP)")
      (footprint "eagle-import:1005")
      (libsource (lib "eagle-import") (part "R1005"))
    )
    (comp (ref "R124")
      (value "22")
      (footprint "eagle-import:3216_ARRAY")
      (libsource (lib "eagle-import") (part "3216_ARRAY"))
    )
    (comp (ref "R125")
      (value "10k")
      (footprint "eagle-import:3216_ARRAY")
      (libsource (lib "eagle-import") (part "3216_ARRAY"))
    )
    (comp (ref "R126")
      (value "22")
      (footprint "eagle-import:1005")
      (libsource (lib "eagle-import") (part "R1005"))
    )
    (comp (ref "R127")
      (value "22")
      (footprint "eagle-import:1005")
      (libsource (lib "eagle-import") (part "R1005"))
    )
    (comp (ref "R128")
      (value "22")
      (footprint "eagle-import:3216_ARRAY")
      (libsource (lib "eagle-import") (part "3216_ARRAY"))
    )
    (comp (ref "R129")
      (value "22")
      (footprint "eagle-import:1005")
      (libsource (lib "eagle-import") (part "R1005"))
    )
    (comp (ref "R130")
      (value "100k")
      (footprint "eagle-import:1005")
      (libsource (lib "eagle-import") (part "R1005"))
    )
    (comp (ref "R131")
      (value "100k")
      (footprint "eagle-import:1005")
      (libsource (lib "eagle-import") (part "R1005"))
    )
    (comp (ref "R132")
      (value "22")
      (footprint "eagle-import:3216_ARRAY")
      (libsource (lib "eagle-import") (part "3216_ARRAY"))
    )
    (comp (ref "R133")
      (value "22")
      (footprint "eagle-import:1005")
      (libsource (lib "eagle-import") (part "R1005"))
    )
    (comp (ref "R134")
      (value "22")
      (footprint "eagle-import:1005")
      (libsource (lib "eagle-import") (part "R1005"))
    )
    (comp (ref "R135")
      (value "22")
      (footprint "eagle-import:1005")
      (libsource (lib "eagle-import") (part "R1005"))
    )
    (comp (ref "R136")
      (value "100k")
      (footprint "eagle-import:1005")
      (libsource (lib "eagle-import") (part "R1005"))
    )
    (comp (ref "R137")
      (value "22")
      (footprint "eagle-import:1005")
      (libsource (lib "eagle-import") (part "R1005"))
    )
    (comp (ref "R138")
      (value "22")
      (footprint "eagle-import:1005")
      (libsource (lib "eagle-import") (part "R1005"))
    )
    (comp (ref "R139")
      (value "100k")
      (footprint "eagle-import:1005")
      (libsource (lib "eagle-import") (part "R1005"))
    )
    (comp (ref "R140")
      (value "100k (DNP)")
      (footprint "eagle-import:1005")
      (libsource (lib "eagle-import") (part "R1005"))
    )
    (comp (ref "SW101")
      (value "SKRHABE010")
      (footprint "eagle-import:SKRH")
      (libsource (lib "eagle-import") (part "SKRHE010AB"))
    )
    (comp (ref "SW102")
      (value "SKQYACE010")
      (footprint "eagle-import:SKQYA")
      (libsource (lib "eagle-import") (part "SKQYAE010C"))
    )
    (comp (ref "U101")
      (value "MCP1416T-E/OT")
      (footprint "eagle-import:SOT23-5")
      (libsource (lib "eagle-import") (part "MCP1416?T-E/OT"))
    )
    (comp (ref "U102")
      (value "MCP6001T-I/LT")
      (footprint "eagle-import:SOT-70-5")
      (libsource (lib "eagle-import") (part "MCP6001?-TI/LT"))
    )
    (comp (ref "U103")
      (value "MCP6001T-I/LT")
      (footprint "eagle-import:SOT-70-5")
      (libsource (lib "eagle-import") (part "MCP6001?-TI/LT"))
    )
    (comp (ref "U104")
      (value "R5F564MLDDFP#V1-ND")
      (footprint "eagle-import:TQFP100-16X16")
      (libsource (lib "eagle-import") (part "R5F564MDFP#V1-NDLD"))
    )
    (comp (ref "U105")
      (value "MR20H40CDF")
      (footprint "eagle-import:8DFN")
      (libsource (lib "eagle-import") (part "MR2H40CDF0"))
    )
    (comp (ref "VR101")
      (value "SV01A103AEA01")
      (footprint "eagle-import:SV01")
      (libsource (lib "eagle-import") (part "SV01A?A01103AE"))
    )
    (comp (ref "X101")
      (value "NX3225SA-12.000M-STD-CSR-1")
      (footprint "eagle-import:3225")
      (libsource (lib "eagle-import") (part "NX3225SA-M-STD-CSR-112.000"))
    )
  )
  (nets
    (net (code "1") (name "+3V3") (class "Default")
      (node (ref "C101") (pin "P$1") (pinfunction "P$1_P$1") (pintype "passive"))
      (node (ref "C102") (pin "P$1") (pinfunction "P$1_P$1") (pintype "passive"))
      (node (ref "C103") (pin "P$1") (pinfunction "P$1_P$1") (pintype "passive"))
      (node (ref "C104") (pin "P$1") (pinfunction "P$1_P$1") (pintype "passive"))
      (node (ref "C105") (pin "P$1") (pinfunction "P$1_P$1") (pintype "passive"))
      (node (ref "C107") (pin "P$1") (pinfunction "P$1_P$1") (pintype "passive"))
      (node (ref "C109") (pin "P$1") (pinfunction "P$1_P$1") (pintype "passive"))
      (node (ref "C110") (pin "P$1") (pinfunction "P$1_P$1") (pintype "passive"))
      (node (ref "C111") (pin "P$1") (pinfunction "P$1_P$1") (pintype "passive"))
      (node (ref "C114") (pin "P$1") (pinfunction "P$1_P$1") (pintype "passive"))
      (node (ref "C115") (pin "P$1") (pinfunction "P$1_P$1") (pintype "passive"))
      (node (ref "C116") (pin "P$1") (pinfunction "P$1_P$1") (pintype "passive"))
      (node (ref "C120") (pin "P$1") (pinfunction "P$1_P$1") (pintype "passive"))
      (node (ref "C204") (pin "P$1") (pinfunction "P$1_P$1") (pintype "passive"))
      (node (ref "C206") (pin "PLUS") (pinfunction "PLUS_PLUS") (pintype "passive"))
      (node (ref "C306") (pin "P$1") (pinfunction "P$1_P$1") (pintype "passive"))
      (node (ref "C312") (pin "P$1") (pinfunction "P$1_P$1") (pintype "passive"))
      (node (ref "C318") (pin "P$1") (pinfunction "P$1_P$1") (pintype "passive"))
      (node (ref "C403") (pin "P$1") (pinfunction "P$1_P$1") (pintype "passive"))
      (node (ref "C406") (pin "P$1") (pinfunction "P$1_P$1") (pintype "passive"))
      (node (ref "C407") (pin "P$1") (pinfunction "P$1_P$1") (pintype "passive"))
      (node (ref "C501") (pin "P$1") (pinfunction "P$1_P$1") (pintype "passive"))
      (node (ref "C502") (pin "P$1") (pinfunction "P$1_P$1") (pintype "passive"))
      (node (ref "C503") (pin "P$1") (pinfunction "P$1_P$1") (pintype "passive"))
      (node (ref "D102") (pin "K") (pinfunction "K_K") (pintype "passive"))
      (node (ref "J101") (pin "8") (pinfunction "8_8") (pintype "bidirectional"))
      (node (ref "J102") (pin "1") (pinfunction "1_1") (pintype "bidirectional"))
      (node (ref "J103") (pin "1") (pinfunction "1_1") (pintype "passive"))
      (node (ref "J104") (pin "4") (pinfunction "4_VDD_4") (pintype "bidirectional"))
      (node (ref "J106") (pin "2") (pinfunction "2_2") (pintype "bidirectional"))
      (node (ref "J401") (pin "4") (pinfunction "4_4") (pintype "bidirectional"))
      (node (ref "PI401") (pin "COLLECTOR") (pinfunction "COLLECTOR_COLLECTOR") (pintype "passive"))
      (node (ref "PI402") (pin "COLLECTOR") (pinfunction "COLLECTOR_COLLECTOR") (pintype "passive"))
      (node (ref "R101") (pin "P$2") (pinfunction "P$2_P$2") (pintype "passive"))
      (node (ref "R102") (pin "R1-B") (pinfunction "R1-B_R1-B") (pintype "passive"))
      (node (ref "R102") (pin "R2-B") (pinfunction "R2-B_R2-B") (pintype "passive"))
      (node (ref "R102") (pin "R3-B") (pinfunction "R3-B_R3-B") (pintype "passive"))
      (node (ref "R102") (pin "R4-B") (pinfunction "R4-B_R4-B") (pintype "passive"))
      (node (ref "R103") (pin "R1-B") (pinfunction "R1-B_R1-B") (pintype "passive"))
      (node (ref "R103") (pin "R2-B") (pinfunction "R2-B_R2-B") (pintype "passive"))
      (node (ref "R103") (pin "R3-B") (pinfunction "R3-B_R3-B") (pintype "passive"))
      (node (ref "R103") (pin "R4-B") (pinfunction "R4-B_R4-B") (pintype "passive"))
      (node (ref "R104") (pin "P$2") (pinfunction "P$2_P$2") (pintype "passive"))
      (node (ref "R108") (pin "P$2") (pinfunction "P$2_P$2") (pintype "passive"))
      (node (ref "R109") (pin "P$2") (pinfunction "P$2_P$2") (pintype "passive"))
      (node (ref "R113") (pin "P$2") (pinfunction "P$2_P$2") (pintype "passive"))
      (node (ref "R114") (pin "P$2") (pinfunction "P$2_P$2") (pintype "passive"))
      (node (ref "R119") (pin "R1-A") (pinfunction "R1-A_R1-A") (pintype "passive"))
      (node (ref "R119") (pin "R2-A") (pinfunction "R2-A_R2-A") (pintype "passive"))
      (node (ref "R120") (pin "R1-A") (pinfunction "R1-A_R1-A") (pintype "passive"))
      (node (ref "R120") (pin "R2-A") (pinfunction "R2-A_R2-A") (pintype "passive"))
      (node (ref "R120") (pin "R3-A") (pinfunction "R3-A_R3-A") (pintype "passive"))
      (node (ref "R130") (pin "P$2") (pinfunction "P$2_P$2") (pintype "passive"))
      (node (ref "R131") (pin "P$2") (pinfunction "P$2_P$2") (pintype "passive"))
      (node (ref "R136") (pin "P$2") (pinfunction "P$2_P$2") (pintype "passive"))
      (node (ref "R139") (pin "P$1") (pinfunction "P$1_P$1") (pintype "passive"))
      (node (ref "R204") (pin "P$2") (pinfunction "P$2_P$2") (pintype "passive"))
      (node (ref "U102") (pin "5") (pinfunction "V+_5") (pintype "power_in"))
      (node (ref "U103") (pin "5") (pinfunction "V+_5") (pintype "power_in"))
      (node (ref "U104") (pin "1") (pinfunction "1_AVCC1_1") (pintype "bidirectional"))
      (node (ref "U104") (pin "14") (pinfunction "14_VCC_14") (pintype "bidirectional"))
      (node (ref "U104") (pin "35") (pinfunction "35_VCC_USB_35") (pintype "bidirectional"))
      (node (ref "U104") (pin "60") (pinfunction "60_VCC_60") (pintype "bidirectional"))
      (node (ref "U104") (pin "96") (pinfunction "96_VREFH0_96") (pintype "bidirectional"))
      (node (ref "U104") (pin "97") (pinfunction "97_AVCC0_97") (pintype "bidirectional"))
      (node (ref "U105") (pin "8") (pinfunction "VDD_8") (pintype "input"))
      (node (ref "U202") (pin "5") (pinfunction "OUT1_5") (pintype "output"))
      (node (ref "U202") (pin "6") (pinfunction "OUT2_6") (pintype "output"))
      (node (ref "U202") (pin "7") (pinfunction "OUT3_7") (pintype "output"))
      (node (ref "U202") (pin "PAD") (pinfunction "OUT_PAD_PAD") (pintype "output"))
      (node (ref "U301") (pin "8") (pinfunction "VCC_8") (pintype "power_in"))
      (node (ref "U303") (pin "8") (pinfunction "VCC_8") (pintype "power_in"))
      (node (ref "U305") (pin "8") (pinfunction "VCC_8") (pintype "power_in"))
      (node (ref "U402") (pin "5") (pinfunction "V+_5") (pintype "power_in"))
      (node (ref "U405") (pin "5") (pinfunction "V+_5") (pintype "power_in"))
      (node (ref "U501") (pin "1") (pinfunction "1_VDDIO_1") (pintype "power_in"))
      (node (ref "U501") (pin "16") (pinfunction "16_VDD_16") (pintype "power_in"))
      (node (ref "VR101") (pin "2") (pinfunction "2_2") (pintype "passive"))
    )
    (net (code "2") (name "+5V") (class "Default")
      (node (ref "C106") (pin "P$1") (pinfunction "P$1_P$1") (pintype "passive"))
      (node (ref "C118") (pin "P$1") (pinfunction "P$1_P$1") (pintype "passive"))
      (node (ref "C201") (pin "P$1") (pinfunction "P$1_P$1") (pintype "passive"))
      (node (ref "C203") (pin "PLUS") (pinfunction "PLUS_PLUS") (pintype "passive"))
      (node (ref "C305") (pin "P$1") (pinfunction "P$1_P$1") (pintype "passive"))
      (node (ref "C308") (pin "P$1") (pinfunction "P$1_P$1") (pintype "passive"))
      (node (ref "C401") (pin "P$1") (pinfunction "P$1_P$1") (pintype "passive"))
      (node (ref "C402") (pin "P$1") (pinfunction "P$1_P$1") (pintype "passive"))
      (node (ref "C404") (pin "P$1") (pinfunction "P$1_P$1") (pintype "passive"))
      (node (ref "C405") (pin "P$1") (pinfunction "P$1_P$1") (pintype "passive"))
      (node (ref "C408") (pin "P$1") (pinfunction "P$1_P$1") (pintype "passive"))
      (node (ref "J106") (pin "1") (pinfunction "1_1") (pintype "bidirectional"))
      (node (ref "J301") (pin "3") (pinfunction "P$3_3") (pintype "passive"))
      (node (ref "J302") (pin "3") (pinfunction "P$3_3") (pintype "passive"))
      (node (ref "R125") (pin "R1-B") (pinfunction "R1-B_R1-B") (pintype "passive"))
      (node (ref "R125") (pin "R2-B") (pinfunction "R2-B_R2-B") (pintype "passive"))
      (node (ref "R125") (pin "R3-B") (pinfunction "R3-B_R3-B") (pintype "passive"))
      (node (ref "R125") (pin "R4-B") (pinfunction "R4-B_R4-B") (pintype "passive"))
      (node (ref "R202") (pin "P$2") (pinfunction "P$2_P$2") (pintype "passive"))
      (node (ref "U101") (pin "2") (pinfunction "VDD_2") (pintype "passive"))
      (node (ref "U201") (pin "5") (pinfunction "OUT1_5") (pintype "output"))
      (node (ref "U201") (pin "6") (pinfunction "OUT2_6") (pintype "output"))
      (node (ref "U201") (pin "7") (pinfunction "OUT3_7") (pintype "output"))
      (node (ref "U201") (pin "PAD") (pinfunction "OUT_PAD_PAD") (pintype "output"))
      (node (ref "U401") (pin "2") (pinfunction "VDD_2") (pintype "passive"))
      (node (ref "U403") (pin "2") (pinfunction "VDD_2") (pintype "passive"))
      (node (ref "U404") (pin "2") (pinfunction "VDD_2") (pintype "passive"))
    )
    (net (code "3") (name "+8V") (class "Default")
      (node (ref "C119") (pin "P$1") (pinfunction "P$1_P$1") (pintype "passive"))
      (node (ref "C202") (pin "P$1") (pinfunction "P$1_P$1") (pintype "passive"))
      (node (ref "C205") (pin "P$1") (pinfunction "P$1_P$1") (pintype "passive"))
      (node (ref "C302") (pin "PLUS") (pinfunction "PLUS_PLUS") (pintype "passive"))
      (node (ref "C315") (pin "PLUS") (pinfunction "PLUS_PLUS") (pintype "passive"))
      (node (ref "J105") (pin "1") (pinfunction "1_1") (pintype "bidirectional"))
      (node (ref "Q201") (pin "5") (pinfunction "D_5") (pintype "passive"))
      (node (ref "Q201") (pin "9") (pinfunction "D_9") (pintype "passive"))
      (node (ref "Q301") (pin "2") (pinfunction "D1_2") (pintype "passive"))
      (node (ref "Q301") (pin "3") (pinfunction "D1_3") (pintype "passive"))
      (node (ref "Q301") (pin "4") (pinfunction "D1_4") (pintype "passive"))
      (node (ref "Q301") (pin "PAD_S") (pinfunction "D1_PAD_S") (pintype "passive"))
      (node (ref "Q302") (pin "2") (pinfunction "D1_2") (pintype "passive"))
      (node (ref "Q302") (pin "3") (pinfunction "D1_3") (pintype "passive"))
      (node (ref "Q302") (pin "4") (pinfunction "D1_4") (pintype "passive"))
      (node (ref "Q302") (pin "PAD_S") (pinfunction "D1_PAD_S") (pintype "passive"))
      (node (ref "Q303") (pin "2") (pinfunction "D1_2") (pintype "passive"))
      (node (ref "Q303") (pin "3") (pinfunction "D1_3") (pintype "passive"))
      (node (ref "Q303") (pin "4") (pinfunction "D1_4") (pintype "passive"))
      (node (ref "Q303") (pin "PAD_S") (pinfunction "D1_PAD_S") (pintype "passive"))
      (node (ref "Q304") (pin "2") (pinfunction "D1_2") (pintype "passive"))
      (node (ref "Q304") (pin "3") (pinfunction "D1_3") (pintype "passive"))
      (node (ref "Q304") (pin "4") (pinfunction "D1_4") (pintype "passive"))
      (node (ref "Q304") (pin "PAD_S") (pinfunction "D1_PAD_S") (pintype "passive"))
      (node (ref "Q305") (pin "2") (pinfunction "D1_2") (pintype "passive"))
      (node (ref "Q305") (pin "3") (pinfunction "D1_3") (pintype "passive"))
      (node (ref "Q305") (pin "4") (pinfunction "D1_4") (pintype "passive"))
      (node (ref "Q305") (pin "PAD_S") (pinfunction "D1_PAD_S") (pintype "passive"))
      (node (ref "Q306") (pin "2") (pinfunction "D1_2") (pintype "passive"))
      (node (ref "Q306") (pin "3") (pinfunction "D1_3") (pintype "passive"))
      (node (ref "Q306") (pin "4") (pinfunction "D1_4") (pintype "passive"))
      (node (ref "Q306") (pin "PAD_S") (pinfunction "D1_PAD_S") (pintype "passive"))
      (node (ref "R107") (pin "P$2") (pinfunction "P$2_P$2") (pintype "passive"))
      (node (ref "R203") (pin "P$2") (pinfunction "P$2_P$2") (pintype "passive"))
      (node (ref "R301") (pin "P$2") (pinfunction "P$2_P$2") (pintype "passive"))
      (node (ref "R313") (pin "P$2") (pinfunction "P$2_P$2") (pintype "passive"))
      (node (ref "R324") (pin "P$2") (pinfunction "P$2_P$2") (pintype "passive"))
      (node (ref "U201") (pin "2") (pinfunction "IN1_2") (pintype "power_in"))
      (node (ref "U201") (pin "3") (pinfunction "IN2_3") (pintype "power_in"))
      (node (ref "U201") (pin "4") (pinfunction "IN3_4") (pintype "power_in"))
      (node (ref "U202") (pin "2") (pinfunction "IN1_2") (pintype "power_in"))
      (node (ref "U202") (pin "3") (pinfunction "IN2_3") (pintype "power_in"))
      (node (ref "U202") (pin "4") (pinfunction "IN3_4") (pintype "power_in"))
    )
    (net (code "4") (name "7_RESV") (class "Default")
      (node (ref "U501") (pin "7") (pinfunction "7_RESV_7") (pintype "power_in"))
    )
    (net (code "5") (name "AD_LINE_L_SEN") (class "Default")
      (node (ref "J401") (pin "1") (pinfunction "1_1") (pintype "bidirectional"))
      (node (ref "U104") (pin "89") (pinfunction "89_P45_89") (pintype "bidirectional"))
    )
    (net (code "6") (name "AD_LINE_R_SEN") (class "Default")
      (node (ref "J401") (pin "6") (pinfunction "6_6") (pintype "bidirectional"))
      (node (ref "U104") (pin "91") (pinfunction "91_P43_91") (pintype "bidirectional"))
    )
    (net (code "7") (name "AD_MARKER_L_SEN") (class "Default")
      (node (ref "U104") (pin "93") (pinfunction "93_P41_93") (pintype "bidirectional"))
      (node (ref "U402") (pin "1") (pinfunction "OUT_1") (pintype "output"))
      (node (ref "U402") (pin "4") (pinfunction "-IN_4") (pintype "input"))
    )
    (net (code "8") (name "AD_MARKER_R_SEN") (class "Default")
      (node (ref "U104") (pin "95") (pinfunction "95_P40_95") (pintype "bidirectional"))
      (node (ref "U405") (pin "1") (pinfunction "OUT_1") (pintype "output"))
      (node (ref "U405") (pin "4") (pinfunction "-IN_4") (pintype "input"))
    )
    (net (code "9") (name "AD_POT") (class "Default")
      (node (ref "U103") (pin "1") (pinfunction "OUT_1") (pintype "output"))
      (node (ref "U103") (pin "4") (pinfunction "-IN_4") (pintype "input"))
      (node (ref "U104") (pin "90") (pinfunction "90_P44_90") (pintype "bidirectional"))
    )
    (net (code "10") (name "AD_POW") (class "Default")
      (node (ref "U102") (pin "1") (pinfunction "OUT_1") (pintype "output"))
      (node (ref "U102") (pin "4") (pinfunction "-IN_4") (pintype "input"))
      (node (ref "U104") (pin "92") (pinfunction "92_P42_92") (pintype "bidirectional"))
    )
    (net (code "11") (name "AD_SUB0") (class "Default")
      (node (ref "U104") (pin "88") (pinfunction "88_P46_88") (pintype "bidirectional"))
    )
    (net (code "12") (name "AD_SUB1") (class "Default")
      (node (ref "U104") (pin "87") (pinfunction "87_P47_87") (pintype "bidirectional"))
    )
    (net (code "13") (name "CPU_SPI_MOSI") (class "Default")
      (node (ref "R116") (pin "P$2") (pinfunction "P$2_P$2") (pintype "passive"))
      (node (ref "R122") (pin "P$2") (pinfunction "P$2_P$2") (pintype "passive"))
      (node (ref "U104") (pin "64") (pinfunction "64_PA6_64") (pintype "bidirectional"))
    )
    (net (code "14") (name "CPU_SPI_SCK") (class "Default")
      (node (ref "R115") (pin "P$2") (pinfunction "P$2_P$2") (pintype "passive"))
      (node (ref "R126") (pin "P$2") (pinfunction "P$2_P$2") (pintype "passive"))
      (node (ref "U104") (pin "65") (pinfunction "65_PA5_65") (pintype "bidirectional"))
    )
    (net (code "15") (name "DRIVE_MOTOR_EN") (class "Default")
      (node (ref "R305") (pin "P$1") (pinfunction "P$1_P$1") (pintype "passive"))
      (node (ref "U104") (pin "58") (pinfunction "58_PB2_58") (pintype "bidirectional"))
      (node (ref "U302") (pin "4") (pinfunction "4_EN2_4") (pintype "bidirectional"))
      (node (ref "U302") (pin "5") (pinfunction "5_EN1_5") (pintype "bidirectional"))
      (node (ref "U304") (pin "4") (pinfunction "4_EN2_4") (pintype "bidirectional"))
      (node (ref "U304") (pin "5") (pinfunction "5_EN1_5") (pintype "bidirectional"))
    )
    (net (code "16") (name "EMLE") (class "Default")
      (node (ref "J101") (pin "4") (pinfunction "4_4") (pintype "bidirectional"))
      (node (ref "R106") (pin "P$2") (pinfunction "P$2_P$2") (pintype "passive"))
      (node (ref "U104") (pin "2") (pinfunction "2_EMLE_2") (pintype "bidirectional"))
    )
    (net (code "17") (name "GND") (class "Default")
      (node (ref "B101") (pin "-") (pinfunction "-_-") (pintype "passive"))
      (node (ref "C101") (pin "P$2") (pinfunction "P$2_P$2") (pintype "passive"))
      (node (ref "C102") (pin "P$2") (pinfunction "P$2_P$2") (pintype "passive"))
      (node (ref "C103") (pin "P$2") (pinfunction "P$2_P$2") (pintype "passive"))
      (node (ref "C104") (pin "P$2") (pinfunction "P$2_P$2") (pintype "passive"))
      (node (ref "C105") (pin "P$2") (pinfunction "P$2_P$2") (pintype "passive"))
      (node (ref "C106") (pin "P$2") (pinfunction "P$2_P$2") (pintype "passive"))
      (node (ref "C107") (pin "P$2") (pinfunction "P$2_P$2") (pintype "passive"))
      (node (ref "C108") (pin "P$2") (pinfunction "P$2_P$2") (pintype "passive"))
      (node (ref "C109") (pin "P$2") (pinfunction "P$2_P$2") (pintype "passive"))
      (node (ref "C110") (pin "P$2") (pinfunction "P$2_P$2") (pintype "passive"))
      (node (ref "C111") (pin "P$2") (pinfunction "P$2_P$2") (pintype "passive"))
      (node (ref "C112") (pin "P$2") (pinfunction "P$2_P$2") (pintype "passive"))
      (node (ref "C113") (pin "P$2") (pinfunction "P$2_P$2") (pintype "passive"))
      (node (ref "C114") (pin "P$2") (pinfunction "P$2_P$2") (pintype "passive"))
      (node (ref "C115") (pin "P$2") (pinfunction "P$2_P$2") (pintype "passive"))
      (node (ref "C116") (pin "P$2") (pinfunction "P$2_P$2") (pintype "passive"))
      (node (ref "C117") (pin "P$2") (pinfunction "P$2_P$2") (pintype "passive"))
      (node (ref "C118") (pin "P$2") (pinfunction "P$2_P$2") (pintype "passive"))
      (node (ref "C119") (pin "P$2") (pinfunction "P$2_P$2") (pintype "passive"))
      (node (ref "C120") (pin "P$2") (pinfunction "P$2_P$2") (pintype "passive"))
      (node (ref "C201") (pin "P$2") (pinfunction "P$2_P$2") (pintype "passive"))
      (node (ref "C202") (pin "P$2") (pinfunction "P$2_P$2") (pintype "passive"))
      (node (ref "C203") (pin "MINUS") (pinfunction "MINUS_MINUS") (pintype "passive"))
      (node (ref "C204") (pin "P$2") (pinfunction "P$2_P$2") (pintype "passive"))
      (node (ref "C205") (pin "P$2") (pinfunction "P$2_P$2") (pintype "passive"))
      (node (ref "C206") (pin "MINUS") (pinfunction "MINUS_MINUS") (pintype "passive"))
      (node (ref "C301") (pin "P$2") (pinfunction "P$2_P$2") (pintype "passive"))
      (node (ref "C302") (pin "MINUS") (pinfunction "MINUS_MINUS") (pintype "passive"))
      (node (ref "C305") (pin "P$2") (pinfunction "P$2_P$2") (pintype "passive"))
      (node (ref "C306") (pin "P$2") (pinfunction "P$2_P$2") (pintype "passive"))
      (node (ref "C308") (pin "P$2") (pinfunction "P$2_P$2") (pintype "passive"))
      (node (ref "C309") (pin "P$2") (pinfunction "P$2_P$2") (pintype "passive"))
      (node (ref "C312") (pin "P$2") (pinfunction "P$2_P$2") (pintype "passive"))
      (node (ref "C314") (pin "P$2") (pinfunction "P$2_P$2") (pintype "passive"))
      (node (ref "C315") (pin "MINUS") (pinfunction "MINUS_MINUS") (pintype "passive"))
      (node (ref "C318") (pin "P$2") (pinfunction "P$2_P$2") (pintype "passive"))
      (node (ref "C401") (pin "P$2") (pinfunction "P$2_P$2") (pintype "passive"))
      (node (ref "C402") (pin "P$2") (pinfunction "P$2_P$2") (pintype "passive"))
      (node (ref "C403") (pin "P$2") (pinfunction "P$2_P$2") (pintype "passive"))
      (node (ref "C404") (pin "P$2") (pinfunction "P$2_P$2") (pintype "passive"))
      (node (ref "C405") (pin "P$2") (pinfunction "P$2_P$2") (pintype "passive"))
      (node (ref "C406") (pin "P$2") (pinfunction "P$2_P$2") (pintype "passive"))
      (node (ref "C407") (pin "P$2") (pinfunction "P$2_P$2") (pintype "passive"))
      (node (ref "C408") (pin "P$2") (pinfunction "P$2_P$2") (pintype "passive"))
      (node (ref "C501") (pin "P$2") (pinfunction "P$2_P$2") (pintype "passive"))
      (node (ref "C502") (pin "P$2") (pinfunction "P$2_P$2") (pintype "passive"))
      (node (ref "C503") (pin "P$2") (pinfunction "P$2_P$2") (pintype "passive"))
      (node (ref "C504") (pin "P$2") (pinfunction "P$2_P$2") (pintype "passive"))
      (node (ref "D101") (pin "A") (pinfunction "A_A") (pintype "passive"))
      (node (ref "J101") (pin "12") (pinfunction "12_12") (pintype "bidirectional"))
      (node (ref "J101") (pin "14") (pinfunction "14_14") (pintype "bidirectional"))
      (node (ref "J101") (pin "2") (pinfunction "2_2") (pintype "bidirectional"))
      (node (ref "J101") (pin "CASE1") (pinfunction "CASE_CASE1") (pintype "bidirectional"))
      (node (ref "J101") (pin "CASE2") (pinfunction "CASE_CASE2") (pintype "bidirectional"))
      (node (ref "J102") (pin "4") (pinfunction "4_4") (pintype "bidirectional"))
      (node (ref "J102") (pin "PAD1") (pinfunction "PAD1_PAD1") (pintype "bidirectional"))
      (node (ref "J102") (pin "PAD2") (pinfunction "PAD2_PAD2") (pintype "bidirectional"))
      (node (ref "J103") (pin "4") (pinfunction "4_4") (pintype "passive"))
      (node (ref "J104") (pin "6") (pinfunction "6_GND_6") (pintype "bidirectional"))
      (node (ref "J105") (pin "4") (pinfunction "4_4") (pintype "bidirectional"))
      (node (ref "J105") (pin "CASE1") (pinfunction "CASE_CASE1") (pintype "bidirectional"))
      (node (ref "J105") (pin "CASE2") (pinfunction "CASE_CASE2") (pintype "bidirectional"))
      (node (ref "J106") (pin "6") (pinfunction "6_6") (pintype "bidirectional"))
      (node (ref "J106") (pin "CASE1") (pinfunction "CASE_CASE1") (pintype "bidirectional"))
      (node (ref "J106") (pin "CASE2") (pinfunction "CASE_CASE2") (pintype "bidirectional"))
      (node (ref "J201") (pin "1") (pinfunction "1_1") (pintype "bidirectional"))
      (node (ref "J201") (pin "CASE_1") (pinfunction "CASE_CASE_1") (pintype "bidirectional"))
      (node (ref "J201") (pin "CASE_2") (pinfunction "CASE_CASE_2") (pintype "bidirectional"))
      (node (ref "J301") (pin "4") (pinfunction "P$4_4") (pintype "passive"))
      (node (ref "J302") (pin "4") (pinfunction "P$4_4") (pintype "passive"))
      (node (ref "J303") (pin "PAD1") (pinfunction "PAD1_PAD1") (pintype "bidirectional"))
      (node (ref "J303") (pin "PAD2") (pinfunction "PAD2_PAD2") (pintype "bidirectional"))
      (node (ref "J401") (pin "2") (pinfunction "2_2") (pintype "bidirectional"))
      (node (ref "J401") (pin "5") (pinfunction "5_5") (pintype "bidirectional"))
      (node (ref "J401") (pin "CASE1") (pinfunction "CASE_CASE1") (pintype "bidirectional"))
      (node (ref "J401") (pin "CASE2") (pinfunction "CASE_CASE2") (pintype "bidirectional"))
      (node (ref "J401") (pin "CASE3") (pinfunction "CASE_CASE3") (pintype "bidirectional"))
      (node (ref "J401") (pin "CASE4") (pinfunction "CASE_CASE4") (pintype "bidirectional"))
      (node (ref "LED201") (pin "K") (pinfunction "K_K") (pintype "passive"))
      (node (ref "LED202") (pin "K") (pinfunction "K_K") (pintype "passive"))
      (node (ref "LED203") (pin "K") (pinfunction "K_K") (pintype "passive"))
      (node (ref "PI401") (pin "CATHODE") (pinfunction "CATHODE_CATHODE") (pintype "passive"))
      (node (ref "PI402") (pin "CATHODE") (pinfunction "CATHODE_CATHODE") (pintype "passive"))
      (node (ref "Q301") (pin "5") (pinfunction "S2_5") (pintype "passive"))
      (node (ref "Q301") (pin "6") (pinfunction "S2_6") (pintype "passive"))
      (node (ref "Q301") (pin "7") (pinfunction "S2_7") (pintype "passive"))
      (node (ref "Q302") (pin "5") (pinfunction "S2_5") (pintype "passive"))
      (node (ref "Q302") (pin "6") (pinfunction "S2_6") (pintype "passive"))
      (node (ref "Q302") (pin "7") (pinfunction "S2_7") (pintype "passive"))
      (node (ref "Q303") (pin "5") (pinfunction "S2_5") (pintype "passive"))
      (node (ref "Q303") (pin "6") (pinfunction "S2_6") (pintype "passive"))
      (node (ref "Q303") (pin "7") (pinfunction "S2_7") (pintype "passive"))
      (node (ref "Q304") (pin "5") (pinfunction "S2_5") (pintype "passive"))
      (node (ref "Q304") (pin "6") (pinfunction "S2_6") (pintype "passive"))
      (node (ref "Q304") (pin "7") (pinfunction "S2_7") (pintype "passive"))
      (node (ref "Q305") (pin "5") (pinfunction "S2_5") (pintype "passive"))
      (node (ref "Q305") (pin "6") (pinfunction "S2_6") (pintype "passive"))
      (node (ref "Q305") (pin "7") (pinfunction "S2_7") (pintype "passive"))
      (node (ref "Q306") (pin "5") (pinfunction "S2_5") (pintype "passive"))
      (node (ref "Q306") (pin "6") (pinfunction "S2_6") (pintype "passive"))
      (node (ref "Q306") (pin "7") (pinfunction "S2_7") (pintype "passive"))
      (node (ref "R105") (pin "P$1") (pinfunction "P$1_P$1") (pintype "passive"))
      (node (ref "R106") (pin "P$1") (pinfunction "P$1_P$1") (pintype "passive"))
      (node (ref "R110") (pin "P$1") (pinfunction "P$1_P$1") (pintype "passive"))
      (node (ref "R111") (pin "P$1") (pinfunction "P$1_P$1") (pintype "passive"))
      (node (ref "R119") (pin "R3-A") (pinfunction "R3-A_R3-A") (pintype "passive"))
      (node (ref "R119") (pin "R4-A") (pinfunction "R4-A_R4-A") (pintype "passive"))
      (node (ref "R140") (pin "P$2") (pinfunction "P$2_P$2") (pintype "passive"))
      (node (ref "R305") (pin "P$2") (pinfunction "P$2_P$2") (pintype "passive"))
      (node (ref "R328") (pin "P$2") (pinfunction "P$2_P$2") (pintype "passive"))
      (node (ref "R402") (pin "P$1") (pinfunction "P$1_P$1") (pintype "passive"))
      (node (ref "R404") (pin "P$1") (pinfunction "P$1_P$1") (pintype "passive"))
      (node (ref "R405") (pin "P$1") (pinfunction "P$1_P$1") (pintype "passive"))
      (node (ref "R502") (pin "P$1") (pinfunction "P$1_P$1") (pintype "passive"))
      (node (ref "SW101") (pin "1") (pinfunction "1_1") (pintype "passive"))
      (node (ref "SW101") (pin "2") (pinfunction "2_2") (pintype "passive"))
      (node (ref "SW101") (pin "COMMON") (pinfunction "COMMON_COMMON") (pintype "passive"))
      (node (ref "SW102") (pin "2") (pinfunction "2_2") (pintype "passive"))
      (node (ref "SW201") (pin "2") (pinfunction "2_2") (pintype "passive"))
      (node (ref "U101") (pin "4") (pinfunction "GND_4") (pintype "passive"))
      (node (ref "U102") (pin "2") (pinfunction "V-_2") (pintype "power_in"))
      (node (ref "U103") (pin "2") (pinfunction "V-_2") (pintype "power_in"))
      (node (ref "U104") (pin "12") (pinfunction "12_VSS_12") (pintype "bidirectional"))
      (node (ref "U104") (pin "3") (pinfunction "3_AVSS1_3") (pintype "bidirectional"))
      (node (ref "U104") (pin "38") (pinfunction "38_VSS_USB_38") (pintype "bidirectional"))
      (node (ref "U104") (pin "62") (pinfunction "62_VSS_62") (pintype "bidirectional"))
      (node (ref "U104") (pin "94") (pinfunction "94_VREFL0_94") (pintype "bidirectional"))
      (node (ref "U104") (pin "99") (pinfunction "99_AVSS0_99") (pintype "bidirectional"))
      (node (ref "U105") (pin "4") (pinfunction "VSS_4") (pintype "input"))
      (node (ref "U105") (pin "PAD") (pinfunction "PAD_PAD") (pintype "input"))
      (node (ref "U201") (pin "1") (pinfunction "ADJ/GND_1") (pintype "passive"))
      (node (ref "U202") (pin "1") (pinfunction "ADJ/GND_1") (pintype "passive"))
      (node (ref "U301") (pin "4") (pinfunction "GND_4") (pintype "power_in"))
      (node (ref "U302") (pin "13") (pinfunction "13_GND_13") (pintype "bidirectional"))
      (node (ref "U302") (pin "17") (pinfunction "17_GND_17") (pintype "bidirectional"))
      (node (ref "U302") (pin "2") (pinfunction "2_GND_2") (pintype "bidirectional"))
      (node (ref "U303") (pin "4") (pinfunction "GND_4") (pintype "power_in"))
      (node (ref "U304") (pin "13") (pinfunction "13_GND_13") (pintype "bidirectional"))
      (node (ref "U304") (pin "17") (pinfunction "17_GND_17") (pintype "bidirectional"))
      (node (ref "U304") (pin "2") (pinfunction "2_GND_2") (pintype "bidirectional"))
      (node (ref "U305") (pin "4") (pinfunction "GND_4") (pintype "power_in"))
      (node (ref "U306") (pin "13") (pinfunction "13_GND_13") (pintype "bidirectional"))
      (node (ref "U306") (pin "17") (pinfunction "17_GND_17") (pintype "bidirectional"))
      (node (ref "U306") (pin "2") (pinfunction "2_GND_2") (pintype "bidirectional"))
      (node (ref "U401") (pin "4") (pinfunction "GND_4") (pintype "passive"))
      (node (ref "U402") (pin "2") (pinfunction "V-_2") (pintype "power_in"))
      (node (ref "U403") (pin "4") (pinfunction "GND_4") (pintype "passive"))
      (node (ref "U404") (pin "4") (pinfunction "GND_4") (pintype "passive"))
      (node (ref "U405") (pin "2") (pinfunction "V-_2") (pintype "power_in"))
      (node (ref "U501") (pin "10") (pinfunction "10_RESV_10") (pintype "power_in"))
      (node (ref "U501") (pin "11") (pinfunction "11_RESV_11") (pintype "output"))
      (node (ref "U501") (pin "12") (pinfunction "12_RESV_12") (pintype "output"))
      (node (ref "U501") (pin "13") (pinfunction "13_GND_13") (pintype "power_in"))
      (node (ref "U501") (pin "15") (pinfunction "15_RESV_15") (pintype "output"))
      (node (ref "U501") (pin "9") (pinfunction "9_RESV_9") (pintype "power_in"))
      (node (ref "VR101") (pin "1") (pinfunction "1_1") (pintype "passive"))
    )
    (net (code "18") (name "G_FSYNC") (class "Default")
      (node (ref "R502") (pin "P$2") (pinfunction "P$2_P$2") (pintype "passive"))
      (node (ref "U104") (pin "67") (pinfunction "67_PA3_67") (pintype "bidirectional"))
      (node (ref "U501") (pin "8") (pinfunction "8_FSYNC_8") (pintype "input"))
    )
    (net (code "19") (name "G_INT") (class "Default")
      (node (ref "U104") (pin "69") (pinfunction "69_PA1_69") (pintype "bidirectional"))
      (node (ref "U501") (pin "6") (pinfunction "6_INT_6") (pintype "output"))
    )
    (net (code "20") (name "IO_SPARE0") (class "Default")
      (node (ref "J106") (pin "3") (pinfunction "3_3") (pintype "bidirectional"))
      (node (ref "U104") (pin "39") (pinfunction "39_P55/TRDATA3_39") (pintype "bidirectional"))
    )
    (net (code "21") (name "IO_SPARE1") (class "Default")
      (node (ref "J106") (pin "4") (pinfunction "4_4") (pintype "bidirectional"))
      (node (ref "U104") (pin "40") (pinfunction "40_P54/TRDATA2_40") (pintype "bidirectional"))
    )
    (net (code "22") (name "IO_SPARE2") (class "Default")
      (node (ref "J106") (pin "5") (pinfunction "5_5") (pintype "bidirectional"))
      (node (ref "U104") (pin "41") (pinfunction "41_P53_41") (pintype "bidirectional"))
    )
    (net (code "23") (name "IO_SPARE3") (class "Default")
      (node (ref "J105") (pin "2") (pinfunction "2_2") (pintype "bidirectional"))
      (node (ref "U104") (pin "47") (pinfunction "47_PC5_47") (pintype "bidirectional"))
    )
    (net (code "24") (name "IO_SPARE4") (class "Default")
      (node (ref "J105") (pin "3") (pinfunction "3_3") (pintype "bidirectional"))
      (node (ref "U104") (pin "48") (pinfunction "48_PC4_48") (pintype "bidirectional"))
    )
    (net (code "25") (name "LED0") (class "Default")
      (node (ref "LED101") (pin "K") (pinfunction "K_K") (pintype "passive"))
      (node (ref "U104") (pin "52") (pinfunction "52_PC0_52") (pintype "bidirectional"))
    )
    (net (code "26") (name "LED1") (class "Default")
      (node (ref "LED102") (pin "K") (pinfunction "K_K") (pintype "passive"))
      (node (ref "U104") (pin "51") (pinfunction "51_PC1_51") (pintype "bidirectional"))
    )
    (net (code "27") (name "LED2") (class "Default")
      (node (ref "LED103") (pin "K") (pinfunction "K_K") (pintype "passive"))
      (node (ref "U104") (pin "50") (pinfunction "50_PC2_50") (pintype "bidirectional"))
    )
    (net (code "28") (name "LED3") (class "Default")
      (node (ref "LED104") (pin "K") (pinfunction "K_K") (pintype "passive"))
      (node (ref "U104") (pin "49") (pinfunction "49_PC3_49") (pintype "bidirectional"))
    )
    (net (code "29") (name "LED_SUB0") (class "Default")
      (node (ref "U104") (pin "34") (pinfunction "34_P12_34") (pintype "bidirectional"))
    )
    (net (code "30") (name "LED_SUB1") (class "Default")
      (node (ref "U104") (pin "33") (pinfunction "33_P13_33") (pintype "bidirectional"))
    )
    (net (code "31") (name "LEFT_MOTOR_CCW") (class "Default")
      (node (ref "U104") (pin "86") (pinfunction "86_PD0_86") (pintype "bidirectional"))
      (node (ref "U301") (pin "1") (pinfunction "I0_1") (pintype "input"))
    )
    (net (code "32") (name "LEFT_MOTOR_CW") (class "Default")
      (node (ref "U104") (pin "85") (pinfunction "85_PD1_85") (pintype "bidirectional"))
      (node (ref "U301") (pin "6") (pinfunction "I1_6") (pintype "input"))
    )
    (net (code "33") (name "LEFT_MOTOR_PWM") (class "Default")
      (node (ref "R137") (pin "P$1") (pinfunction "P$1_P$1") (pintype "passive"))
      (node (ref "U301") (pin "2") (pinfunction "I1_2") (pintype "input"))
      (node (ref "U301") (pin "5") (pinfunction "I0_5") (pintype "input"))
    )
    (net (code "34") (name "LEFT_TCLKC") (class "Default")
      (node (ref "R307") (pin "P$2") (pinfunction "P$2_P$2") (pintype "passive"))
      (node (ref "R308") (pin "P$2") (pinfunction "P$2_P$2") (pintype "passive"))
      (node (ref "U104") (pin "26") (pinfunction "26_P22_26") (pintype "bidirectional"))
    )
    (net (code "35") (name "LEFT_TCLKD") (class "Default")
      (node (ref "R309") (pin "P$2") (pinfunction "P$2_P$2") (pintype "passive"))
      (node (ref "R311") (pin "P$2") (pinfunction "P$2_P$2") (pintype "passive"))
      (node (ref "U104") (pin "25") (pinfunction "25_P23_25") (pintype "bidirectional"))
    )
    (net (code "36") (name "MD{slash}FINE") (class "Default")
      (node (ref "J101") (pin "7") (pinfunction "7_7") (pintype "bidirectional"))
      (node (ref "R102") (pin "R2-A") (pinfunction "R2-A_R2-A") (pintype "passive"))
      (node (ref "U104") (pin "7") (pinfunction "7_MD/FINED_7") (pintype "bidirectional"))
    )
    (net (code "37") (name "MOT1_OUTA") (class "Default")
      (node (ref "C303") (pin "P$2") (pinfunction "P$2_P$2") (pintype "passive"))
      (node (ref "C304") (pin "P$1") (pinfunction "P$1_P$1") (pintype "passive"))
      (node (ref "J301") (pin "2") (pinfunction "P$2_2") (pintype "passive"))
      (node (ref "Q301") (pin "PAD_L") (pinfunction "S1D2_PAD_L") (pintype "passive"))
      (node (ref "U302") (pin "15") (pinfunction "15_PHASE2_15") (pintype "bidirectional"))
    )
    (net (code "38") (name "MOT1_OUTB") (class "Default")
      (node (ref "C304") (pin "P$2") (pinfunction "P$2_P$2") (pintype "passive"))
      (node (ref "C307") (pin "P$2") (pinfunction "P$2_P$2") (pintype "passive"))
      (node (ref "J301") (pin "1") (pinfunction "P$1_1") (pintype "passive"))
      (node (ref "Q302") (pin "PAD_L") (pinfunction "S1D2_PAD_L") (pintype "passive"))
      (node (ref "U302") (pin "10") (pinfunction "10_PHASE1_10") (pintype "bidirectional"))
    )
    (net (code "39") (name "MOT2_OUTA") (class "Default")
      (node (ref "C310") (pin "P$2") (pinfunction "P$2_P$2") (pintype "passive"))
      (node (ref "C311") (pin "P$1") (pinfunction "P$1_P$1") (pintype "passive"))
      (node (ref "J302") (pin "2") (pinfunction "P$2_2") (pintype "passive"))
      (node (ref "Q303") (pin "PAD_L") (pinfunction "S1D2_PAD_L") (pintype "passive"))
      (node (ref "U304") (pin "15") (pinfunction "15_PHASE2_15") (pintype "bidirectional"))
    )
    (net (code "40") (name "MOT2_OUTB") (class "Default")
      (node (ref "C311") (pin "P$2") (pinfunction "P$2_P$2") (pintype "passive"))
      (node (ref "C313") (pin "P$2") (pinfunction "P$2_P$2") (pintype "passive"))
      (node (ref "J302") (pin "1") (pinfunction "P$1_1") (pintype "passive"))
      (node (ref "Q304") (pin "PAD_L") (pinfunction "S1D2_PAD_L") (pintype "passive"))
      (node (ref "U304") (pin "10") (pinfunction "10_PHASE1_10") (pintype "bidirectional"))
    )
    (net (code "41") (name "Net-(B101-Pad+)") (class "Default")
      (node (ref "B101") (pin "+") (pinfunction "+_+") (pintype "passive"))
      (node (ref "D101") (pin "K") (pinfunction "K_K") (pintype "passive"))
      (node (ref "R112") (pin "P$1") (pinfunction "P$1_P$1") (pintype "passive"))
    )
    (net (code "42") (name "Net-(C303-PadP$1)") (class "Default")
      (node (ref "C303") (pin "P$1") (pinfunction "P$1_P$1") (pintype "passive"))
      (node (ref "R303") (pin "P$1") (pinfunction "P$1_P$1") (pintype "passive"))
    )
    (net (code "43") (name "Net-(C307-PadP$1)") (class "Default")
      (node (ref "C307") (pin "P$1") (pinfunction "P$1_P$1") (pintype "passive"))
      (node (ref "R312") (pin "P$1") (pinfunction "P$1_P$1") (pintype "passive"))
    )
    (net (code "44") (name "Net-(C310-PadP$1)") (class "Default")
      (node (ref "C310") (pin "P$1") (pinfunction "P$1_P$1") (pintype "passive"))
      (node (ref "R318") (pin "P$1") (pinfunction "P$1_P$1") (pintype "passive"))
    )
    (net (code "45") (name "Net-(C313-PadP$1)") (class "Default")
      (node (ref "C313") (pin "P$1") (pinfunction "P$1_P$1") (pintype "passive"))
      (node (ref "R323") (pin "P$1") (pinfunction "P$1_P$1") (pintype "passive"))
    )
    (net (code "46") (name "Net-(C316-PadP$1)") (class "Default")
      (node (ref "C316") (pin "P$1") (pinfunction "P$1_P$1") (pintype "passive"))
      (node (ref "R326") (pin "P$1") (pinfunction "P$1_P$1") (pintype "passive"))
    )
    (net (code "47") (name "Net-(C319-PadP$1)") (class "Default")
      (node (ref "C319") (pin "P$1") (pinfunction "P$1_P$1") (pintype "passive"))
      (node (ref "R331") (pin "P$1") (pinfunction "P$1_P$1") (pintype "passive"))
    )
    (net (code "48") (name "Net-(J104-1_NC{slash}DAT2)") (class "Default")
      (node (ref "J104") (pin "1") (pinfunction "1_NC/DAT2_1") (pintype "bidirectional"))
      (node (ref "R124") (pin "R4-A") (pinfunction "R4-A_R4-A") (pintype "passive"))
    )
    (net (code "49") (name "Net-(J104-2_-CS{slash}DAT3)") (class "Default")
      (node (ref "J104") (pin "2") (pinfunction "2_-CS/DAT3_2") (pintype "bidirectional"))
      (node (ref "R124") (pin "R3-A") (pinfunction "R3-A_R3-A") (pintype "passive"))
    )
    (net (code "50") (name "Net-(J104-3_DI{slash}CMD)") (class "Default")
      (node (ref "J104") (pin "3") (pinfunction "3_DI/CMD_3") (pintype "bidirectional"))
      (node (ref "R124") (pin "R2-A") (pinfunction "R2-A_R2-A") (pintype "passive"))
    )
    (net (code "51") (name "Net-(J104-5_CLK)") (class "Default")
      (node (ref "J104") (pin "5") (pinfunction "5_CLK_5") (pintype "bidirectional"))
      (node (ref "R124") (pin "R1-A") (pinfunction "R1-A_R1-A") (pintype "passive"))
    )
    (net (code "52") (name "Net-(J104-7_DO{slash}DAT0)") (class "Default")
      (node (ref "J104") (pin "7") (pinfunction "7_DO/DAT0_7") (pintype "bidirectional"))
      (node (ref "R128") (pin "R4-A") (pinfunction "R4-A_R4-A") (pintype "passive"))
    )
    (net (code "53") (name "Net-(J104-8_RSV{slash}DAT1)") (class "Default")
      (node (ref "J104") (pin "8") (pinfunction "8_RSV/DAT1_8") (pintype "bidirectional"))
      (node (ref "R128") (pin "R3-A") (pinfunction "R3-A_R3-A") (pintype "passive"))
    )
    (net (code "54") (name "Net-(J104-CD1)") (class "Default")
      (node (ref "J104") (pin "CD") (pinfunction "CD1_CD") (pintype "bidirectional"))
      (node (ref "R128") (pin "R2-A") (pinfunction "R2-A_R2-A") (pintype "passive"))
    )
    (net (code "55") (name "Net-(J301-P$5)") (class "Default")
      (node (ref "J301") (pin "5") (pinfunction "P$5_5") (pintype "passive"))
      (node (ref "R307") (pin "P$1") (pinfunction "P$1_P$1") (pintype "passive"))
    )
    (net (code "56") (name "Net-(J301-P$6)") (class "Default")
      (node (ref "J301") (pin "6") (pinfunction "P$6_6") (pintype "passive"))
      (node (ref "R308") (pin "P$1") (pinfunction "P$1_P$1") (pintype "passive"))
    )
    (net (code "57") (name "Net-(J301-P$7)") (class "Default")
      (node (ref "J301") (pin "7") (pinfunction "P$7_7") (pintype "passive"))
      (node (ref "R309") (pin "P$1") (pinfunction "P$1_P$1") (pintype "passive"))
    )
    (net (code "58") (name "Net-(J301-P$8)") (class "Default")
      (node (ref "J301") (pin "8") (pinfunction "P$8_8") (pintype "passive"))
      (node (ref "R311") (pin "P$1") (pinfunction "P$1_P$1") (pintype "passive"))
    )
    (net (code "59") (name "Net-(J302-P$5)") (class "Default")
      (node (ref "J302") (pin "5") (pinfunction "P$5_5") (pintype "passive"))
      (node (ref "R314") (pin "P$1") (pinfunction "P$1_P$1") (pintype "passive"))
    )
    (net (code "60") (name "Net-(J302-P$6)") (class "Default")
      (node (ref "J302") (pin "6") (pinfunction "P$6_6") (pintype "passive"))
      (node (ref "R315") (pin "P$1") (pinfunction "P$1_P$1") (pintype "passive"))
    )
    (net (code "61") (name "Net-(J302-P$7)") (class "Default")
      (node (ref "J302") (pin "7") (pinfunction "P$7_7") (pintype "passive"))
      (node (ref "R317") (pin "P$1") (pinfunction "P$1_P$1") (pintype "passive"))
    )
    (net (code "62") (name "Net-(J302-P$8)") (class "Default")
      (node (ref "J302") (pin "8") (pinfunction "P$8_8") (pintype "passive"))
      (node (ref "R319") (pin "P$1") (pinfunction "P$1_P$1") (pintype "passive"))
    )
    (net (code "63") (name "Net-(LED101-PadA)") (class "Default")
      (node (ref "LED101") (pin "A") (pinfunction "A_A") (pintype "passive"))
      (node (ref "R125") (pin "R1-A") (pinfunction "R1-A_R1-A") (pintype "passive"))
    )
    (net (code "64") (name "Net-(LED102-PadA)") (class "Default")
      (node (ref "LED102") (pin "A") (pinfunction "A_A") (pintype "passive"))
      (node (ref "R125") (pin "R2-A") (pinfunction "R2-A_R2-A") (pintype "passive"))
    )
    (net (code "65") (name "Net-(LED103-PadA)") (class "Default")
      (node (ref "LED103") (pin "A") (pinfunction "A_A") (pintype "passive"))
      (node (ref "R125") (pin "R3-A") (pinfunction "R3-A_R3-A") (pintype "passive"))
    )
    (net (code "66") (name "Net-(LED104-PadA)") (class "Default")
      (node (ref "LED104") (pin "A") (pinfunction "A_A") (pintype "passive"))
      (node (ref "R125") (pin "R4-A") (pinfunction "R4-A_R4-A") (pintype "passive"))
    )
    (net (code "67") (name "Net-(LED201-PadA)") (class "Default")
      (node (ref "LED201") (pin "A") (pinfunction "A_A") (pintype "passive"))
      (node (ref "R202") (pin "P$1") (pinfunction "P$1_P$1") (pintype "passive"))
    )
    (net (code "68") (name "Net-(LED202-PadA)") (class "Default")
      (node (ref "LED202") (pin "A") (pinfunction "A_A") (pintype "passive"))
      (node (ref "R203") (pin "P$1") (pinfunction "P$1_P$1") (pintype "passive"))
    )
    (net (code "69") (name "Net-(LED203-PadA)") (class "Default")
      (node (ref "LED203") (pin "A") (pinfunction "A_A") (pintype "passive"))
      (node (ref "R204") (pin "P$1") (pinfunction "P$1_P$1") (pintype "passive"))
    )
    (net (code "70") (name "Net-(PI401-PadANODE)") (class "Default")
      (node (ref "PI401") (pin "ANODE") (pinfunction "ANODE_ANODE") (pintype "passive"))
      (node (ref "R401") (pin "P$1") (pinfunction "P$1_P$1") (pintype "passive"))
    )
    (net (code "71") (name "Net-(PI402-PadANODE)") (class "Default")
      (node (ref "PI402") (pin "ANODE") (pinfunction "ANODE_ANODE") (pintype "passive"))
      (node (ref "R403") (pin "P$1") (pinfunction "P$1_P$1") (pintype "passive"))
    )
    (net (code "72") (name "Net-(Q201-G)") (class "Default")
      (node (ref "Q201") (pin "4") (pinfunction "G_4") (pintype "passive"))
      (node (ref "R201") (pin "P$1") (pinfunction "P$1_P$1") (pintype "passive"))
      (node (ref "SW201") (pin "1") (pinfunction "1_1") (pintype "passive"))
    )
    (net (code "73") (name "Net-(Q301-G1)") (class "Default")
      (node (ref "Q301") (pin "1") (pinfunction "G1_1") (pintype "passive"))
      (node (ref "R302") (pin "P$1") (pinfunction "P$1_P$1") (pintype "passive"))
    )
    (net (code "74") (name "Net-(Q301-G2)") (class "Default")
      (node (ref "Q301") (pin "8") (pinfunction "G2_8") (pintype "passive"))
      (node (ref "R304") (pin "P$1") (pinfunction "P$1_P$1") (pintype "passive"))
    )
    (net (code "75") (name "Net-(Q302-G1)") (class "Default")
      (node (ref "Q302") (pin "1") (pinfunction "G1_1") (pintype "passive"))
      (node (ref "R306") (pin "P$1") (pinfunction "P$1_P$1") (pintype "passive"))
    )
    (net (code "76") (name "Net-(Q302-G2)") (class "Default")
      (node (ref "Q302") (pin "8") (pinfunction "G2_8") (pintype "passive"))
      (node (ref "R310") (pin "P$1") (pinfunction "P$1_P$1") (pintype "passive"))
    )
    (net (code "77") (name "Net-(Q303-G1)") (class "Default")
      (node (ref "Q303") (pin "1") (pinfunction "G1_1") (pintype "passive"))
      (node (ref "R316") (pin "P$1") (pinfunction "P$1_P$1") (pintype "passive"))
    )
    (net (code "78") (name "Net-(Q303-G2)") (class "Default")
      (node (ref "Q303") (pin "8") (pinfunction "G2_8") (pintype "passive"))
      (node (ref "R320") (pin "P$1") (pinfunction "P$1_P$1") (pintype "passive"))
    )
    (net (code "79") (name "Net-(Q304-G1)") (class "Default")
      (node (ref "Q304") (pin "1") (pinfunction "G1_1") (pintype "passive"))
      (node (ref "R321") (pin "P$1") (pinfunction "P$1_P$1") (pintype "passive"))
    )
    (net (code "80") (name "Net-(Q304-G2)") (class "Default")
      (node (ref "Q304") (pin "8") (pinfunction "G2_8") (pintype "passive"))
      (node (ref "R322") (pin "P$1") (pinfunction "P$1_P$1") (pintype "passive"))
    )
    (net (code "81") (name "Net-(Q305-G1)") (class "Default")
      (node (ref "Q305") (pin "1") (pinfunction "G1_1") (pintype "passive"))
      (node (ref "R325") (pin "P$1") (pinfunction "P$1_P$1") (pintype "passive"))
    )
    (net (code "82") (name "Net-(Q305-G2)") (class "Default")
      (node (ref "Q305") (pin "8") (pinfunction "G2_8") (pintype "passive"))
      (node (ref "R327") (pin "P$1") (pinfunction "P$1_P$1") (pintype "passive"))
    )
    (net (code "83") (name "Net-(Q305-S1D2)") (class "Default")
      (node (ref "C316") (pin "P$2") (pinfunction "P$2_P$2") (pintype "passive"))
      (node (ref "C317") (pin "P$1") (pinfunction "P$1_P$1") (pintype "passive"))
      (node (ref "J303") (pin "1") (pinfunction "1_1") (pintype "bidirectional"))
      (node (ref "Q305") (pin "PAD_L") (pinfunction "S1D2_PAD_L") (pintype "passive"))
      (node (ref "U306") (pin "15") (pinfunction "15_PHASE2_15") (pintype "bidirectional"))
    )
    (net (code "84") (name "Net-(Q306-G1)") (class "Default")
      (node (ref "Q306") (pin "1") (pinfunction "G1_1") (pintype "passive"))
      (node (ref "R329") (pin "P$1") (pinfunction "P$1_P$1") (pintype "passive"))
    )
    (net (code "85") (name "Net-(Q306-G2)") (class "Default")
      (node (ref "Q306") (pin "8") (pinfunction "G2_8") (pintype "passive"))
      (node (ref "R330") (pin "P$1") (pinfunction "P$1_P$1") (pintype "passive"))
    )
    (net (code "86") (name "Net-(Q306-S1D2)") (class "Default")
      (node (ref "C317") (pin "P$2") (pinfunction "P$2_P$2") (pintype "passive"))
      (node (ref "C319") (pin "P$2") (pinfunction "P$2_P$2") (pintype "passive"))
      (node (ref "J303") (pin "2") (pinfunction "2_2") (pintype "bidirectional"))
      (node (ref "Q306") (pin "PAD_L") (pinfunction "S1D2_PAD_L") (pintype "passive"))
      (node (ref "U306") (pin "10") (pinfunction "10_PHASE1_10") (pintype "bidirectional"))
    )
    (net (code "87") (name "Net-(U101-OUT)") (class "Default")
      (node (ref "R112") (pin "P$2") (pinfunction "P$2_P$2") (pintype "passive"))
      (node (ref "U101") (pin "5") (pinfunction "OUT_5") (pintype "passive"))
    )
    (net (code "88") (name "Net-(U102A-+IN)") (class "Default")
      (node (ref "R107") (pin "P$1") (pinfunction "P$1_P$1") (pintype "passive"))
      (node (ref "R110") (pin "P$2") (pinfunction "P$2_P$2") (pintype "passive"))
      (node (ref "U102") (pin "3") (pinfunction "+IN_3") (pintype "input"))
    )
    (net (code "89") (name "Net-(U103A-+IN)") (class "Default")
      (node (ref "U103") (pin "3") (pinfunction "+IN_3") (pintype "input"))
      (node (ref "VR101") (pin "3") (pinfunction "3_3") (pintype "passive"))
      (node (ref "VR101") (pin "4") (pinfunction "4_4") (pintype "passive"))
    )
    (net (code "90") (name "Net-(U104-5_VCL)") (class "Default")
      (node (ref "C108") (pin "P$1") (pinfunction "P$1_P$1") (pintype "passive"))
      (node (ref "U104") (pin "5") (pinfunction "5_VCL_5") (pintype "bidirectional"))
    )
    (net (code "91") (name "Net-(U104-11_P37{slash}XTAL)") (class "Default")
      (node (ref "C112") (pin "P$1") (pinfunction "P$1_P$1") (pintype "passive"))
      (node (ref "U104") (pin "11") (pinfunction "11_P37/XTAL_11") (pintype "bidirectional"))
      (node (ref "X101") (pin "3") (pinfunction "3_3") (pintype "bidirectional"))
    )
    (net (code "92") (name "Net-(U104-13_P36{slash}EXTAL)") (class "Default")
      (node (ref "C113") (pin "P$1") (pinfunction "P$1_P$1") (pintype "passive"))
      (node (ref "U104") (pin "13") (pinfunction "13_P36/EXTAL_13") (pintype "bidirectional"))
      (node (ref "X101") (pin "1") (pinfunction "1_1") (pintype "bidirectional"))
    )
    (net (code "93") (name "Net-(U104-36_USB0_DM)") (class "Default")
      (node (ref "R118") (pin "P$1") (pinfunction "P$1_P$1") (pintype "passive"))
      (node (ref "U104") (pin "36") (pinfunction "36_USB0_DM_36") (pintype "bidirectional"))
    )
    (net (code "94") (name "Net-(U104-37_USB0_DP)") (class "Default")
      (node (ref "R117") (pin "P$1") (pinfunction "P$1_P$1") (pintype "passive"))
      (node (ref "U104") (pin "37") (pinfunction "37_USB0_DP_37") (pintype "bidirectional"))
    )
    (net (code "95") (name "Net-(U104-46_PC6)") (class "Default")
      (node (ref "R129") (pin "P$2") (pinfunction "P$2_P$2") (pintype "passive"))
      (node (ref "U104") (pin "46") (pinfunction "46_PC6_46") (pintype "bidirectional"))
    )
    (net (code "96") (name "Net-(U104-57_PB3)") (class "Default")
      (node (ref "R123") (pin "P$2") (pinfunction "P$2_P$2") (pintype "passive"))
      (node (ref "U104") (pin "57") (pinfunction "57_PB3_57") (pintype "bidirectional"))
    )
    (net (code "97") (name "Net-(U104-76_PE2)") (class "Default")
      (node (ref "R138") (pin "P$2") (pinfunction "P$2_P$2") (pintype "passive"))
      (node (ref "U104") (pin "76") (pinfunction "76_PE2_76") (pintype "bidirectional"))
    )
    (net (code "98") (name "Net-(U104-77_PE1)") (class "Default")
      (node (ref "R137") (pin "P$2") (pinfunction "P$2_P$2") (pintype "passive"))
      (node (ref "U104") (pin "77") (pinfunction "77_PE1_77") (pintype "bidirectional"))
    )
    (net (code "99") (name "Net-(U104-79_PD7)") (class "Default")
      (node (ref "R135") (pin "P$2") (pinfunction "P$2_P$2") (pintype "passive"))
      (node (ref "U104") (pin "79") (pinfunction "79_PD7_79") (pintype "bidirectional"))
    )
    (net (code "100") (name "Net-(U104-80_PD6)") (class "Default")
      (node (ref "R133") (pin "P$2") (pinfunction "P$2_P$2") (pintype "passive"))
      (node (ref "U104") (pin "80") (pinfunction "80_PD6_80") (pintype "bidirectional"))
    )
    (net (code "101") (name "Net-(U104-81_PD5)") (class "Default")
      (node (ref "R132") (pin "R1-B") (pinfunction "R1-B_R1-B") (pintype "passive"))
      (node (ref "U104") (pin "81") (pinfunction "81_PD5_81") (pintype "bidirectional"))
    )
    (net (code "102") (name "Net-(U104-82_PD4)") (class "Default")
      (node (ref "R132") (pin "R2-B") (pinfunction "R2-B_R2-B") (pintype "passive"))
      (node (ref "U104") (pin "82") (pinfunction "82_PD4_82") (pintype "bidirectional"))
    )
    (net (code "103") (name "Net-(U104-83_PD3)") (class "Default")
      (node (ref "R132") (pin "R3-B") (pinfunction "R3-B_R3-B") (pintype "passive"))
      (node (ref "U104") (pin "83") (pinfunction "83_PD3_83") (pintype "bidirectional"))
    )
    (net (code "104") (name "Net-(U104-84_PD2)") (class "Default")
      (node (ref "R132") (pin "R4-B") (pinfunction "R4-B_R4-B") (pintype "passive"))
      (node (ref "U104") (pin "84") (pinfunction "84_PD2_84") (pintype "bidirectional"))
    )
    (net (code "105") (name "Net-(U105-DO)") (class "Default")
      (node (ref "R134") (pin "P$2") (pinfunction "P$2_P$2") (pintype "passive"))
      (node (ref "U105") (pin "2") (pinfunction "DO_2") (pintype "tri_state"))
    )
    (net (code "106") (name "Net-(U105-~{HOLD})") (class "Default")
      (node (ref "R131") (pin "P$1") (pinfunction "P$1_P$1") (pintype "passive"))
      (node (ref "U105") (pin "7") (pinfunction "~{HOLD}_7") (pintype "input"))
    )
    (net (code "107") (name "Net-(U105-~{WP})") (class "Default")
      (node (ref "R130") (pin "P$1") (pinfunction "P$1_P$1") (pintype "passive"))
      (node (ref "U105") (pin "3") (pinfunction "~{WP}_3") (pintype "input"))
    )
    (net (code "108") (name "Net-(U301A-O)") (class "Default")
      (node (ref "U301") (pin "7") (pinfunction "O_7") (pintype "output"))
      (node (ref "U302") (pin "3") (pinfunction "3_PWM2_3") (pintype "bidirectional"))
    )
    (net (code "109") (name "Net-(U301B-O)") (class "Default")
      (node (ref "U301") (pin "3") (pinfunction "O_3") (pintype "output"))
      (node (ref "U302") (pin "6") (pinfunction "6_PWM1_6") (pintype "bidirectional"))
    )
    (net (code "110") (name "Net-(U302-1_BOOT2)") (class "Default")
      (node (ref "R303") (pin "P$2") (pinfunction "P$2_P$2") (pintype "passive"))
      (node (ref "U302") (pin "1") (pinfunction "1_BOOT2_1") (pintype "bidirectional"))
    )
    (net (code "111") (name "Net-(U302-8_BOOT1)") (class "Default")
      (node (ref "R312") (pin "P$2") (pinfunction "P$2_P$2") (pintype "passive"))
      (node (ref "U302") (pin "8") (pinfunction "8_BOOT1_8") (pintype "bidirectional"))
    )
    (net (code "112") (name "Net-(U302-9_UGATE1)") (class "Default")
      (node (ref "R306") (pin "P$2") (pinfunction "P$2_P$2") (pintype "passive"))
      (node (ref "U302") (pin "9") (pinfunction "9_UGATE1_9") (pintype "bidirectional"))
    )
    (net (code "113") (name "Net-(U302-11_LGATE1)") (class "Default")
      (node (ref "R310") (pin "P$2") (pinfunction "P$2_P$2") (pintype "passive"))
      (node (ref "U302") (pin "11") (pinfunction "11_LGATE1_11") (pintype "bidirectional"))
    )
    (net (code "114") (name "Net-(U302-12_VCC)") (class "Default")
      (node (ref "C301") (pin "P$1") (pinfunction "P$1_P$1") (pintype "passive"))
      (node (ref "R301") (pin "P$1") (pinfunction "P$1_P$1") (pintype "passive"))
      (node (ref "U302") (pin "12") (pinfunction "12_VCC_12") (pintype "bidirectional"))
    )
    (net (code "115") (name "Net-(U302-14_LGATE2)") (class "Default")
      (node (ref "R304") (pin "P$2") (pinfunction "P$2_P$2") (pintype "passive"))
      (node (ref "U302") (pin "14") (pinfunction "14_LGATE2_14") (pintype "bidirectional"))
    )
    (net (code "116") (name "Net-(U302-16_UGATE2)") (class "Default")
      (node (ref "R302") (pin "P$2") (pinfunction "P$2_P$2") (pintype "passive"))
      (node (ref "U302") (pin "16") (pinfunction "16_UGATE2_16") (pintype "bidirectional"))
    )
    (net (code "117") (name "Net-(U303A-O)") (class "Default")
      (node (ref "U303") (pin "7") (pinfunction "O_7") (pintype "output"))
      (node (ref "U304") (pin "3") (pinfunction "3_PWM2_3") (pintype "bidirectional"))
    )
    (net (code "118") (name "Net-(U303B-O)") (class "Default")
      (node (ref "U303") (pin "3") (pinfunction "O_3") (pintype "output"))
      (node (ref "U304") (pin "6") (pinfunction "6_PWM1_6") (pintype "bidirectional"))
    )
    (net (code "119") (name "Net-(U304-1_BOOT2)") (class "Default")
      (node (ref "R318") (pin "P$2") (pinfunction "P$2_P$2") (pintype "passive"))
      (node (ref "U304") (pin "1") (pinfunction "1_BOOT2_1") (pintype "bidirectional"))
    )
    (net (code "120") (name "Net-(U304-8_BOOT1)") (class "Default")
      (node (ref "R323") (pin "P$2") (pinfunction "P$2_P$2") (pintype "passive"))
      (node (ref "U304") (pin "8") (pinfunction "8_BOOT1_8") (pintype "bidirectional"))
    )
    (net (code "121") (name "Net-(U304-9_UGATE1)") (class "Default")
      (node (ref "R321") (pin "P$2") (pinfunction "P$2_P$2") (pintype "passive"))
      (node (ref "U304") (pin "9") (pinfunction "9_UGATE1_9") (pintype "bidirectional"))
    )
    (net (code "122") (name "Net-(U304-11_LGATE1)") (class "Default")
      (node (ref "R322") (pin "P$2") (pinfunction "P$2_P$2") (pintype "passive"))
      (node (ref "U304") (pin "11") (pinfunction "11_LGATE1_11") (pintype "bidirectional"))
    )
    (net (code "123") (name "Net-(U304-12_VCC)") (class "Default")
      (node (ref "C309") (pin "P$1") (pinfunction "P$1_P$1") (pintype "passive"))
      (node (ref "R313") (pin "P$1") (pinfunction "P$1_P$1") (pintype "passive"))
      (node (ref "U304") (pin "12") (pinfunction "12_VCC_12") (pintype "bidirectional"))
    )
    (net (code "124") (name "Net-(U304-14_LGATE2)") (class "Default")
      (node (ref "R320") (pin "P$2") (pinfunction "P$2_P$2") (pintype "passive"))
      (node (ref "U304") (pin "14") (pinfunction "14_LGATE2_14") (pintype "bidirectional"))
    )
    (net (code "125") (name "Net-(U304-16_UGATE2)") (class "Default")
      (node (ref "R316") (pin "P$2") (pinfunction "P$2_P$2") (pintype "passive"))
      (node (ref "U304") (pin "16") (pinfunction "16_UGATE2_16") (pintype "bidirectional"))
    )
    (net (code "126") (name "Net-(U305A-O)") (class "Default")
      (node (ref "U305") (pin "7") (pinfunction "O_7") (pintype "output"))
      (node (ref "U306") (pin "3") (pinfunction "3_PWM2_3") (pintype "bidirectional"))
    )
    (net (code "127") (name "Net-(U305B-O)") (class "Default")
      (node (ref "U305") (pin "3") (pinfunction "O_3") (pintype "output"))
      (node (ref "U306") (pin "6") (pinfunction "6_PWM1_6") (pintype "bidirectional"))
    )
    (net (code "128") (name "Net-(U306-1_BOOT2)") (class "Default")
      (node (ref "R326") (pin "P$2") (pinfunction "P$2_P$2") (pintype "passive"))
      (node (ref "U306") (pin "1") (pinfunction "1_BOOT2_1") (pintype "bidirectional"))
    )
    (net (code "129") (name "Net-(U306-8_BOOT1)") (class "Default")
      (node (ref "R331") (pin "P$2") (pinfunction "P$2_P$2") (pintype "passive"))
      (node (ref "U306") (pin "8") (pinfunction "8_BOOT1_8") (pintype "bidirectional"))
    )
    (net (code "130") (name "Net-(U306-9_UGATE1)") (class "Default")
      (node (ref "R329") (pin "P$2") (pinfunction "P$2_P$2") (pintype "passive"))
      (node (ref "U306") (pin "9") (pinfunction "9_UGATE1_9") (pintype "bidirectional"))
    )
    (net (code "131") (name "Net-(U306-11_LGATE1)") (class "Default")
      (node (ref "R330") (pin "P$2") (pinfunction "P$2_P$2") (pintype "passive"))
      (node (ref "U306") (pin "11") (pinfunction "11_LGATE1_11") (pintype "bidirectional"))
    )
    (net (code "132") (name "Net-(U306-12_VCC)") (class "Default")
      (node (ref "C314") (pin "P$1") (pinfunction "P$1_P$1") (pintype "passive"))
      (node (ref "R324") (pin "P$1") (pinfunction "P$1_P$1") (pintype "passive"))
      (node (ref "U306") (pin "12") (pinfunction "12_VCC_12") (pintype "bidirectional"))
    )
    (net (code "133") (name "Net-(U306-14_LGATE2)") (class "Default")
      (node (ref "R327") (pin "P$2") (pinfunction "P$2_P$2") (pintype "passive"))
      (node (ref "U306") (pin "14") (pinfunction "14_LGATE2_14") (pintype "bidirectional"))
    )
    (net (code "134") (name "Net-(U306-16_UGATE2)") (class "Default")
      (node (ref "R325") (pin "P$2") (pinfunction "P$2_P$2") (pintype "passive"))
      (node (ref "U306") (pin "16") (pinfunction "16_UGATE2_16") (pintype "bidirectional"))
    )
    (net (code "135") (name "Net-(U401-OUT)") (class "Default")
      (node (ref "R401") (pin "P$2") (pinfunction "P$2_P$2") (pintype "passive"))
      (node (ref "U401") (pin "5") (pinfunction "OUT_5") (pintype "passive"))
    )
    (net (code "136") (name "Net-(U402A-+IN)") (class "Default")
      (node (ref "PI401") (pin "EMITTER") (pinfunction "EMITTER_EMITTER") (pintype "passive"))
      (node (ref "R402") (pin "P$2") (pinfunction "P$2_P$2") (pintype "passive"))
      (node (ref "U402") (pin "3") (pinfunction "+IN_3") (pintype "input"))
    )
    (net (code "137") (name "Net-(U403-OUT)") (class "Default")
      (node (ref "R403") (pin "P$2") (pinfunction "P$2_P$2") (pintype "passive"))
      (node (ref "U403") (pin "5") (pinfunction "OUT_5") (pintype "passive"))
    )
    (net (code "138") (name "Net-(U404-OUT)") (class "Default")
      (node (ref "J401") (pin "3") (pinfunction "3_3") (pintype "bidirectional"))
      (node (ref "U404") (pin "5") (pinfunction "OUT_5") (pintype "passive"))
    )
    (net (code "139") (name "Net-(U405A-+IN)") (class "Default")
      (node (ref "PI402") (pin "EMITTER") (pinfunction "EMITTER_EMITTER") (pintype "passive"))
      (node (ref "R405") (pin "P$2") (pinfunction "P$2_P$2") (pintype "passive"))
      (node (ref "U405") (pin "3") (pinfunction "+IN_3") (pintype "input"))
    )
    (net (code "140") (name "Net-(U501-4_SA0{slash}SDO)") (class "Default")
      (node (ref "R501") (pin "P$1") (pinfunction "P$1_P$1") (pintype "passive"))
      (node (ref "U501") (pin "4") (pinfunction "4_SA0/SDO_4") (pintype "bidirectional"))
    )
    (net (code "141") (name "Net-(U501-14_REGOUT)") (class "Default")
      (node (ref "C504") (pin "P$1") (pinfunction "P$1_P$1") (pintype "passive"))
      (node (ref "U501") (pin "14") (pinfunction "14_REGOUT_14") (pintype "passive"))
    )
    (net (code "142") (name "PWM_BUZZER") (class "Default")
      (node (ref "R111") (pin "P$2") (pinfunction "P$2_P$2") (pintype "passive"))
      (node (ref "U101") (pin "3") (pinfunction "IN_3") (pintype "passive"))
      (node (ref "U104") (pin "59") (pinfunction "59_PB1_59") (pintype "bidirectional"))
    )
    (net (code "143") (name "PWM_SUB") (class "Default")
      (node (ref "R123") (pin "P$1") (pinfunction "P$1_P$1") (pintype "passive"))
    )
    (net (code "144") (name "RESET") (class "Default")
      (node (ref "C117") (pin "P$1") (pinfunction "P$1_P$1") (pintype "passive"))
      (node (ref "D102") (pin "A") (pinfunction "A_A") (pintype "passive"))
      (node (ref "J101") (pin "13") (pinfunction "13_13") (pintype "bidirectional"))
      (node (ref "R136") (pin "P$1") (pinfunction "P$1_P$1") (pintype "passive"))
      (node (ref "SW102") (pin "1") (pinfunction "1_1") (pintype "passive"))
      (node (ref "U104") (pin "10") (pinfunction "10_RES#_10") (pintype "bidirectional"))
    )
    (net (code "145") (name "RIGHT_MOTOR_CCW") (class "Default")
      (node (ref "U104") (pin "78") (pinfunction "78_PE0_78") (pintype "bidirectional"))
      (node (ref "U303") (pin "1") (pinfunction "I0_1") (pintype "input"))
    )
    (net (code "146") (name "RIGHT_MOTOR_CW") (class "Default")
      (node (ref "U104") (pin "75") (pinfunction "75_PE3_75") (pintype "bidirectional"))
      (node (ref "U303") (pin "6") (pinfunction "I1_6") (pintype "input"))
    )
    (net (code "147") (name "RIGHT_MOTOR_PWM") (class "Default")
      (node (ref "R138") (pin "P$1") (pinfunction "P$1_P$1") (pintype "passive"))
      (node (ref "U303") (pin "2") (pinfunction "I1_2") (pintype "input"))
      (node (ref "U303") (pin "5") (pinfunction "I0_5") (pintype "input"))
    )
    (net (code "148") (name "RIGHT_TCLKA") (class "Default")
      (node (ref "R314") (pin "P$2") (pinfunction "P$2_P$2") (pintype "passive"))
      (node (ref "R315") (pin "P$2") (pinfunction "P$2_P$2") (pintype "passive"))
      (node (ref "U104") (pin "24") (pinfunction "24_P24_24") (pintype "bidirectional"))
    )
    (net (code "149") (name "RIGHT_TCLKB") (class "Default")
      (node (ref "R317") (pin "P$2") (pinfunction "P$2_P$2") (pintype "passive"))
      (node (ref "R319") (pin "P$2") (pinfunction "P$2_P$2") (pintype "passive"))
      (node (ref "U104") (pin "23") (pinfunction "23_P25_23") (pintype "bidirectional"))
    )
    (net (code "150") (name "RXD2_BTM") (class "Default")
      (node (ref "J103") (pin "3") (pinfunction "3_3") (pintype "passive"))
      (node (ref "R113") (pin "P$1") (pinfunction "P$1_P$1") (pintype "passive"))
      (node (ref "U104") (pin "43") (pinfunction "43_P51_43") (pintype "bidirectional"))
    )
    (net (code "151") (name "RXD9_OLED") (class "Default")
      (node (ref "J102") (pin "3") (pinfunction "3_3") (pintype "bidirectional"))
      (node (ref "R108") (pin "P$1") (pinfunction "P$1_P$1") (pintype "passive"))
      (node (ref "U104") (pin "54") (pinfunction "54_PB6_54") (pintype "bidirectional"))
    )
    (net (code "152") (name "SCK2_BTM") (class "Default")
      (node (ref "U104") (pin "42") (pinfunction "42_P52_42") (pintype "bidirectional"))
    )
    (net (code "153") (name "SCK9_OLED") (class "Default")
      (node (ref "U104") (pin "55") (pinfunction "55_PB5_55") (pintype "bidirectional"))
    )
    (net (code "154") (name "SD_CD") (class "Default")
      (node (ref "R119") (pin "R3-B") (pinfunction "R3-B_R3-B") (pintype "passive"))
      (node (ref "R128") (pin "R2-B") (pinfunction "R2-B_R2-B") (pintype "passive"))
      (node (ref "U104") (pin "72") (pinfunction "72_PE6_72") (pintype "bidirectional"))
    )
    (net (code "155") (name "SD_CLK") (class "Default")
      (node (ref "R124") (pin "R1-B") (pinfunction "R1-B_R1-B") (pintype "passive"))
      (node (ref "R126") (pin "P$1") (pinfunction "P$1_P$1") (pintype "passive"))
      (node (ref "R132") (pin "R1-A") (pinfunction "R1-A_R1-A") (pintype "passive"))
    )
    (net (code "156") (name "SD_CMD") (class "Default")
      (node (ref "R120") (pin "R3-B") (pinfunction "R3-B_R3-B") (pintype "passive"))
      (node (ref "R122") (pin "P$1") (pinfunction "P$1_P$1") (pintype "passive"))
      (node (ref "R124") (pin "R2-B") (pinfunction "R2-B_R2-B") (pintype "passive"))
      (node (ref "R132") (pin "R2-A") (pinfunction "R2-A_R2-A") (pintype "passive"))
    )
    (net (code "157") (name "SD_DAT0") (class "Default")
      (node (ref "R119") (pin "R1-B") (pinfunction "R1-B_R1-B") (pintype "passive"))
      (node (ref "R127") (pin "P$1") (pinfunction "P$1_P$1") (pintype "passive"))
      (node (ref "R128") (pin "R4-B") (pinfunction "R4-B_R4-B") (pintype "passive"))
      (node (ref "R133") (pin "P$1") (pinfunction "P$1_P$1") (pintype "passive"))
    )
    (net (code "158") (name "SD_DAT1") (class "Default")
      (node (ref "R119") (pin "R2-B") (pinfunction "R2-B_R2-B") (pintype "passive"))
      (node (ref "R128") (pin "R3-B") (pinfunction "R3-B_R3-B") (pintype "passive"))
      (node (ref "R135") (pin "P$1") (pinfunction "P$1_P$1") (pintype "passive"))
    )
    (net (code "159") (name "SD_DAT2") (class "Default")
      (node (ref "R120") (pin "R1-B") (pinfunction "R1-B_R1-B") (pintype "passive"))
      (node (ref "R124") (pin "R4-B") (pinfunction "R4-B_R4-B") (pintype "passive"))
      (node (ref "R132") (pin "R4-A") (pinfunction "R4-A_R4-A") (pintype "passive"))
    )
    (net (code "160") (name "SD_DAT3") (class "Default")
      (node (ref "R120") (pin "R2-B") (pinfunction "R2-B_R2-B") (pintype "passive"))
      (node (ref "R121") (pin "P$1") (pinfunction "P$1_P$1") (pintype "passive"))
      (node (ref "R124") (pin "R3-B") (pinfunction "R3-B_R3-B") (pintype "passive"))
      (node (ref "R132") (pin "R3-A") (pinfunction "R3-A_R3-A") (pintype "passive"))
    )
    (net (code "161") (name "SD_WP") (class "Default")
      (node (ref "U104") (pin "71") (pinfunction "71_PE7_71") (pintype "bidirectional"))
    )
    (net (code "162") (name "SENSOR_MOTOR_CCW") (class "Default")
      (node (ref "U104") (pin "74") (pinfunction "74_PE4_74") (pintype "bidirectional"))
      (node (ref "U305") (pin "1") (pinfunction "I0_1") (pintype "input"))
    )
    (net (code "163") (name "SENSOR_MOTOR_CW") (class "Default")
      (node (ref "U104") (pin "61") (pinfunction "61_PB0_61") (pintype "bidirectional"))
      (node (ref "U305") (pin "6") (pinfunction "I1_6") (pintype "input"))
    )
    (net (code "164") (name "SENSOR_MOTOR_EN") (class "Default")
      (node (ref "R328") (pin "P$1") (pinfunction "P$1_P$1") (pintype "passive"))
      (node (ref "U104") (pin "56") (pinfunction "56_PB4_56") (pintype "bidirectional"))
      (node (ref "U306") (pin "4") (pinfunction "4_EN2_4") (pintype "bidirectional"))
      (node (ref "U306") (pin "5") (pinfunction "5_EN1_5") (pintype "bidirectional"))
    )
    (net (code "165") (name "SENSOR_MOTOR_PWM") (class "Default")
      (node (ref "R129") (pin "P$1") (pinfunction "P$1_P$1") (pintype "passive"))
      (node (ref "U305") (pin "2") (pinfunction "I1_2") (pintype "input"))
      (node (ref "U305") (pin "5") (pinfunction "I0_5") (pintype "input"))
    )
    (net (code "166") (name "SEN_GATE") (class "Default")
      (node (ref "R404") (pin "P$2") (pinfunction "P$2_P$2") (pintype "passive"))
      (node (ref "U104") (pin "32") (pinfunction "32_P14_32") (pintype "bidirectional"))
      (node (ref "U401") (pin "3") (pinfunction "IN_3") (pintype "passive"))
      (node (ref "U403") (pin "3") (pinfunction "IN_3") (pintype "passive"))
      (node (ref "U404") (pin "3") (pinfunction "IN_3") (pintype "passive"))
    )
    (net (code "167") (name "SPI_CS0") (class "Default")
      (node (ref "U104") (pin "66") (pinfunction "66_PA4_66") (pintype "bidirectional"))
      (node (ref "U501") (pin "5") (pinfunction "5_NCS_5") (pintype "input"))
    )
    (net (code "168") (name "SPI_CS1") (class "Default")
      (node (ref "U104") (pin "70") (pinfunction "70_PA0_70") (pintype "bidirectional"))
      (node (ref "U105") (pin "1") (pinfunction "~{CS}_1") (pintype "input"))
    )
    (net (code "169") (name "SPI_CS3") (class "Default")
      (node (ref "R121") (pin "P$2") (pinfunction "P$2_P$2") (pintype "passive"))
      (node (ref "U104") (pin "68") (pinfunction "68_PA2_68") (pintype "bidirectional"))
    )
    (net (code "170") (name "SPI_MISO") (class "Default")
      (node (ref "R127") (pin "P$2") (pinfunction "P$2_P$2") (pintype "passive"))
      (node (ref "R134") (pin "P$1") (pinfunction "P$1_P$1") (pintype "passive"))
      (node (ref "R501") (pin "P$2") (pinfunction "P$2_P$2") (pintype "passive"))
      (node (ref "U104") (pin "63") (pinfunction "63_PA7_63") (pintype "bidirectional"))
    )
    (net (code "171") (name "SPI_MOSI") (class "Default")
      (node (ref "R116") (pin "P$1") (pinfunction "P$1_P$1") (pintype "passive"))
      (node (ref "U105") (pin "5") (pinfunction "DI_5") (pintype "input"))
      (node (ref "U501") (pin "3") (pinfunction "3_SDA/SDI_3") (pintype "bidirectional"))
    )
    (net (code "172") (name "SPI_SCK") (class "Default")
      (node (ref "R115") (pin "P$1") (pinfunction "P$1_P$1") (pintype "passive"))
      (node (ref "U105") (pin "6") (pinfunction "CLK_6") (pintype "input"))
      (node (ref "U501") (pin "2") (pinfunction "2_SCL/SCLK_2") (pintype "input"))
    )
    (net (code "173") (name "TACT_A") (class "Default")
      (node (ref "R103") (pin "R1-A") (pinfunction "R1-A_R1-A") (pintype "passive"))
      (node (ref "SW101") (pin "A") (pinfunction "A_A") (pintype "passive"))
      (node (ref "U104") (pin "28") (pinfunction "28_P20_28") (pintype "bidirectional"))
    )
    (net (code "174") (name "TACT_B") (class "Default")
      (node (ref "R103") (pin "R3-A") (pinfunction "R3-A_R3-A") (pintype "passive"))
      (node (ref "SW101") (pin "B") (pinfunction "B_B") (pintype "passive"))
      (node (ref "U104") (pin "29") (pinfunction "29_P17_29") (pintype "bidirectional"))
    )
    (net (code "175") (name "TACT_C") (class "Default")
      (node (ref "R104") (pin "P$1") (pinfunction "P$1_P$1") (pintype "passive"))
      (node (ref "SW101") (pin "C") (pinfunction "C_C") (pintype "passive"))
      (node (ref "U104") (pin "31") (pinfunction "31_P15_31") (pintype "bidirectional"))
    )
    (net (code "176") (name "TACT_CENTER") (class "Default")
      (node (ref "R103") (pin "R2-A") (pinfunction "R2-A_R2-A") (pintype "passive"))
      (node (ref "SW101") (pin "CENTER") (pinfunction "CENTER_CENTER") (pintype "passive"))
      (node (ref "U104") (pin "27") (pinfunction "27_P21_27") (pintype "bidirectional"))
    )
    (net (code "177") (name "TACT_D") (class "Default")
      (node (ref "R103") (pin "R4-A") (pinfunction "R4-A_R4-A") (pintype "passive"))
      (node (ref "SW101") (pin "D") (pinfunction "D_D") (pintype "passive"))
      (node (ref "U104") (pin "30") (pinfunction "30_P16_30") (pintype "bidirectional"))
    )
    (net (code "178") (name "TCK") (class "Default")
      (node (ref "J101") (pin "1") (pinfunction "1_1") (pintype "bidirectional"))
      (node (ref "R101") (pin "P$1") (pinfunction "P$1_P$1") (pintype "passive"))
      (node (ref "U104") (pin "21") (pinfunction "21_P27/TCK_21") (pintype "bidirectional"))
    )
    (net (code "179") (name "TDI") (class "Default")
      (node (ref "J101") (pin "11") (pinfunction "11_11") (pintype "bidirectional"))
      (node (ref "R102") (pin "R4-A") (pinfunction "R4-A_R4-A") (pintype "passive"))
      (node (ref "U104") (pin "20") (pinfunction "20_P30/TDI_20") (pintype "bidirectional"))
    )
    (net (code "180") (name "TDO") (class "Default")
      (node (ref "J101") (pin "5") (pinfunction "5_5") (pintype "bidirectional"))
      (node (ref "R102") (pin "R1-A") (pinfunction "R1-A_R1-A") (pintype "passive"))
      (node (ref "U104") (pin "22") (pinfunction "22_P26/TDO_22") (pintype "bidirectional"))
    )
    (net (code "181") (name "TMS") (class "Default")
      (node (ref "J101") (pin "9") (pinfunction "9_9") (pintype "bidirectional"))
      (node (ref "R102") (pin "R3-A") (pinfunction "R3-A_R3-A") (pintype "passive"))
      (node (ref "U104") (pin "19") (pinfunction "19_P31/TMS_19") (pintype "bidirectional"))
    )
    (net (code "182") (name "TRST#") (class "Default")
      (node (ref "J101") (pin "3") (pinfunction "3_3") (pintype "bidirectional"))
      (node (ref "R105") (pin "P$2") (pinfunction "P$2_P$2") (pintype "passive"))
      (node (ref "U104") (pin "16") (pinfunction "16_P34/TRST#_16") (pintype "bidirectional"))
    )
    (net (code "183") (name "TXD2_BTM") (class "Default")
      (node (ref "J103") (pin "2") (pinfunction "2_2") (pintype "passive"))
      (node (ref "R114") (pin "P$1") (pinfunction "P$1_P$1") (pintype "passive"))
      (node (ref "U104") (pin "44") (pinfunction "44_P50_44") (pintype "bidirectional"))
    )
    (net (code "184") (name "TXD9_OLED") (class "Default")
      (node (ref "J102") (pin "2") (pinfunction "2_2") (pintype "bidirectional"))
      (node (ref "R109") (pin "P$1") (pinfunction "P$1_P$1") (pintype "passive"))
      (node (ref "U104") (pin "53") (pinfunction "53_PB7_53") (pintype "bidirectional"))
    )
    (net (code "185") (name "UB") (class "Default")
      (node (ref "J101") (pin "10") (pinfunction "10_10") (pintype "bidirectional"))
      (node (ref "U104") (pin "45") (pinfunction "45_PC7/UB_45") (pintype "bidirectional"))
    )
    (net (code "186") (name "UPSEL_NMI") (class "Default")
      (node (ref "R139") (pin "P$2") (pinfunction "P$2_P$2") (pintype "passive"))
      (node (ref "R140") (pin "P$1") (pinfunction "P$1_P$1") (pintype "passive"))
      (node (ref "U104") (pin "15") (pinfunction "15_P35/UPSEL/NMI_15") (pintype "bidirectional"))
    )
    (net (code "187") (name "USB0_DM") (class "Default")
      (node (ref "R118") (pin "P$2") (pinfunction "P$2_P$2") (pintype "passive"))
    )
    (net (code "188") (name "USB0_DP") (class "Default")
      (node (ref "R117") (pin "P$2") (pinfunction "P$2_P$2") (pintype "passive"))
    )
    (net (code "189") (name "VCC") (class "Default")
      (node (ref "J201") (pin "2") (pinfunction "2_2") (pintype "bidirectional"))
      (node (ref "Q201") (pin "1") (pinfunction "S_1") (pintype "passive"))
      (node (ref "R201") (pin "P$2") (pinfunction "P$2_P$2") (pintype "passive"))
    )
    (net (code "190") (name "unconnected-(B101-PadNC)") (class "Default")
      (node (ref "B101") (pin "NC") (pinfunction "NC_NC") (pintype "no_connect"))
    )
    (net (code "191") (name "unconnected-(J101-Pad6)") (class "Default")
      (node (ref "J101") (pin "6") (pinfunction "6_6") (pintype "bidirectional"))
    )
    (net (code "192") (name "unconnected-(J104-SHIELD-PadGND1)") (class "Default")
      (node (ref "J104") (pin "GND1") (pinfunction "SHIELD_GND1") (pintype "bidirectional"))
    )
    (net (code "193") (name "unconnected-(J104-SHIELD-PadGND2)") (class "Default")
      (node (ref "J104") (pin "GND2") (pinfunction "SHIELD_GND2") (pintype "bidirectional"))
    )
    (net (code "194") (name "unconnected-(J104-SHIELD-PadGND3)") (class "Default")
      (node (ref "J104") (pin "GND3") (pinfunction "SHIELD_GND3") (pintype "bidirectional"))
    )
    (net (code "195") (name "unconnected-(J104-SHIELD-PadGND4)") (class "Default")
      (node (ref "J104") (pin "GND4") (pinfunction "SHIELD_GND4") (pintype "bidirectional"))
    )
    (net (code "196") (name "unconnected-(J301-P$9-Pad9)") (class "Default")
      (node (ref "J301") (pin "9") (pinfunction "P$9_9") (pintype "passive"))
    )
    (net (code "197") (name "unconnected-(J301-P$10-Pad10)") (class "Default")
      (node (ref "J301") (pin "10") (pinfunction "P$10_10") (pintype "passive"))
    )
    (net (code "198") (name "unconnected-(J302-P$9-Pad9)") (class "Default")
      (node (ref "J302") (pin "9") (pinfunction "P$9_9") (pintype "passive"))
    )
    (net (code "199") (name "unconnected-(J302-P$10-Pad10)") (class "Default")
      (node (ref "J302") (pin "10") (pinfunction "P$10_10") (pintype "passive"))
    )
    (net (code "200") (name "unconnected-(R119-PadR4-B)") (class "Default")
      (node (ref "R119") (pin "R4-B") (pinfunction "R4-B_R4-B") (pintype "passive"))
    )
    (net (code "201") (name "unconnected-(R120-PadR4-A)") (class "Default")
      (node (ref "R120") (pin "R4-A") (pinfunction "R4-A_R4-A") (pintype "passive"))
    )
    (net (code "202") (name "unconnected-(R120-PadR4-B)") (class "Default")
      (node (ref "R120") (pin "R4-B") (pinfunction "R4-B_R4-B") (pintype "passive"))
    )
    (net (code "203") (name "unconnected-(R128-PadR1-A)") (class "Default")
      (node (ref "R128") (pin "R1-A") (pinfunction "R1-A_R1-A") (pintype "passive"))
    )
    (net (code "204") (name "unconnected-(R128-PadR1-B)") (class "Default")
      (node (ref "R128") (pin "R1-B") (pinfunction "R1-B_R1-B") (pintype "passive"))
    )
    (net (code "205") (name "unconnected-(SW201-Pad3)") (class "Default")
      (node (ref "SW201") (pin "3") (pinfunction "3_3") (pintype "passive"))
    )
    (net (code "206") (name "unconnected-(U101-NC-Pad1)") (class "Default")
      (node (ref "U101") (pin "1") (pinfunction "NC_1") (pintype "no_connect"))
    )
    (net (code "207") (name "unconnected-(U104-4_PJ3-Pad4)") (class "Default")
      (node (ref "U104") (pin "4") (pinfunction "4_PJ3_4") (pintype "bidirectional"))
    )
    (net (code "208") (name "unconnected-(U104-6_VBATT-Pad6)") (class "Default")
      (node (ref "U104") (pin "6") (pinfunction "6_VBATT_6") (pintype "bidirectional"))
    )
    (net (code "209") (name "unconnected-(U104-8_XCIN-Pad8)") (class "Default")
      (node (ref "U104") (pin "8") (pinfunction "8_XCIN_8") (pintype "bidirectional"))
    )
    (net (code "210") (name "unconnected-(U104-9_XCOUT-Pad9)") (class "Default")
      (node (ref "U104") (pin "9") (pinfunction "9_XCOUT_9") (pintype "bidirectional"))
    )
    (net (code "211") (name "unconnected-(U104-17_P33-Pad17)") (class "Default")
      (node (ref "U104") (pin "17") (pinfunction "17_P33_17") (pintype "bidirectional"))
    )
    (net (code "212") (name "unconnected-(U104-18_P32-Pad18)") (class "Default")
      (node (ref "U104") (pin "18") (pinfunction "18_P32_18") (pintype "bidirectional"))
    )
    (net (code "213") (name "unconnected-(U104-73_PE5-Pad73)") (class "Default")
      (node (ref "U104") (pin "73") (pinfunction "73_PE5_73") (pintype "bidirectional"))
    )
    (net (code "214") (name "unconnected-(U104-98_P07-Pad98)") (class "Default")
      (node (ref "U104") (pin "98") (pinfunction "98_P07_98") (pintype "bidirectional"))
    )
    (net (code "215") (name "unconnected-(U104-100_P05-Pad100)") (class "Default")
      (node (ref "U104") (pin "100") (pinfunction "100_P05_100") (pintype "bidirectional"))
    )
    (net (code "216") (name "unconnected-(U201-NC-Pad8)") (class "Default")
      (node (ref "U201") (pin "8") (pinfunction "NC_8") (pintype "no_connect"))
    )
    (net (code "217") (name "unconnected-(U202-NC-Pad8)") (class "Default")
      (node (ref "U202") (pin "8") (pinfunction "NC_8") (pintype "no_connect"))
    )
    (net (code "218") (name "unconnected-(U302-7_POR-Pad7)") (class "Default")
      (node (ref "U302") (pin "7") (pinfunction "7_POR_7") (pintype "bidirectional"))
    )
    (net (code "219") (name "unconnected-(U304-7_POR-Pad7)") (class "Default")
      (node (ref "U304") (pin "7") (pinfunction "7_POR_7") (pintype "bidirectional"))
    )
    (net (code "220") (name "unconnected-(U306-7_POR-Pad7)") (class "Default")
      (node (ref "U306") (pin "7") (pinfunction "7_POR_7") (pintype "bidirectional"))
    )
    (net (code "221") (name "unconnected-(U401-NC-Pad1)") (class "Default")
      (node (ref "U401") (pin "1") (pinfunction "NC_1") (pintype "no_connect"))
    )
    (net (code "222") (name "unconnected-(U403-NC-Pad1)") (class "Default")
      (node (ref "U403") (pin "1") (pinfunction "NC_1") (pintype "no_connect"))
    )
    (net (code "223") (name "unconnected-(U404-NC-Pad1)") (class "Default")
      (node (ref "U404") (pin "1") (pinfunction "NC_1") (pintype "no_connect"))
    )
    (net (code "224") (name "unconnected-(X101-Pad2)") (class "Default")
      (node (ref "X101") (pin "2") (pinfunction "2_2") (pintype "passive"))
    )
    (net (code "225") (name "unconnected-(X101-Pad4)") (class "Default")
      (node (ref "X101") (pin "4") (pinfunction "4_4") (pintype "passive"))
    )
  )
)
